# MS.net
KiCad netlist of a schematic drawn in Altium Designer
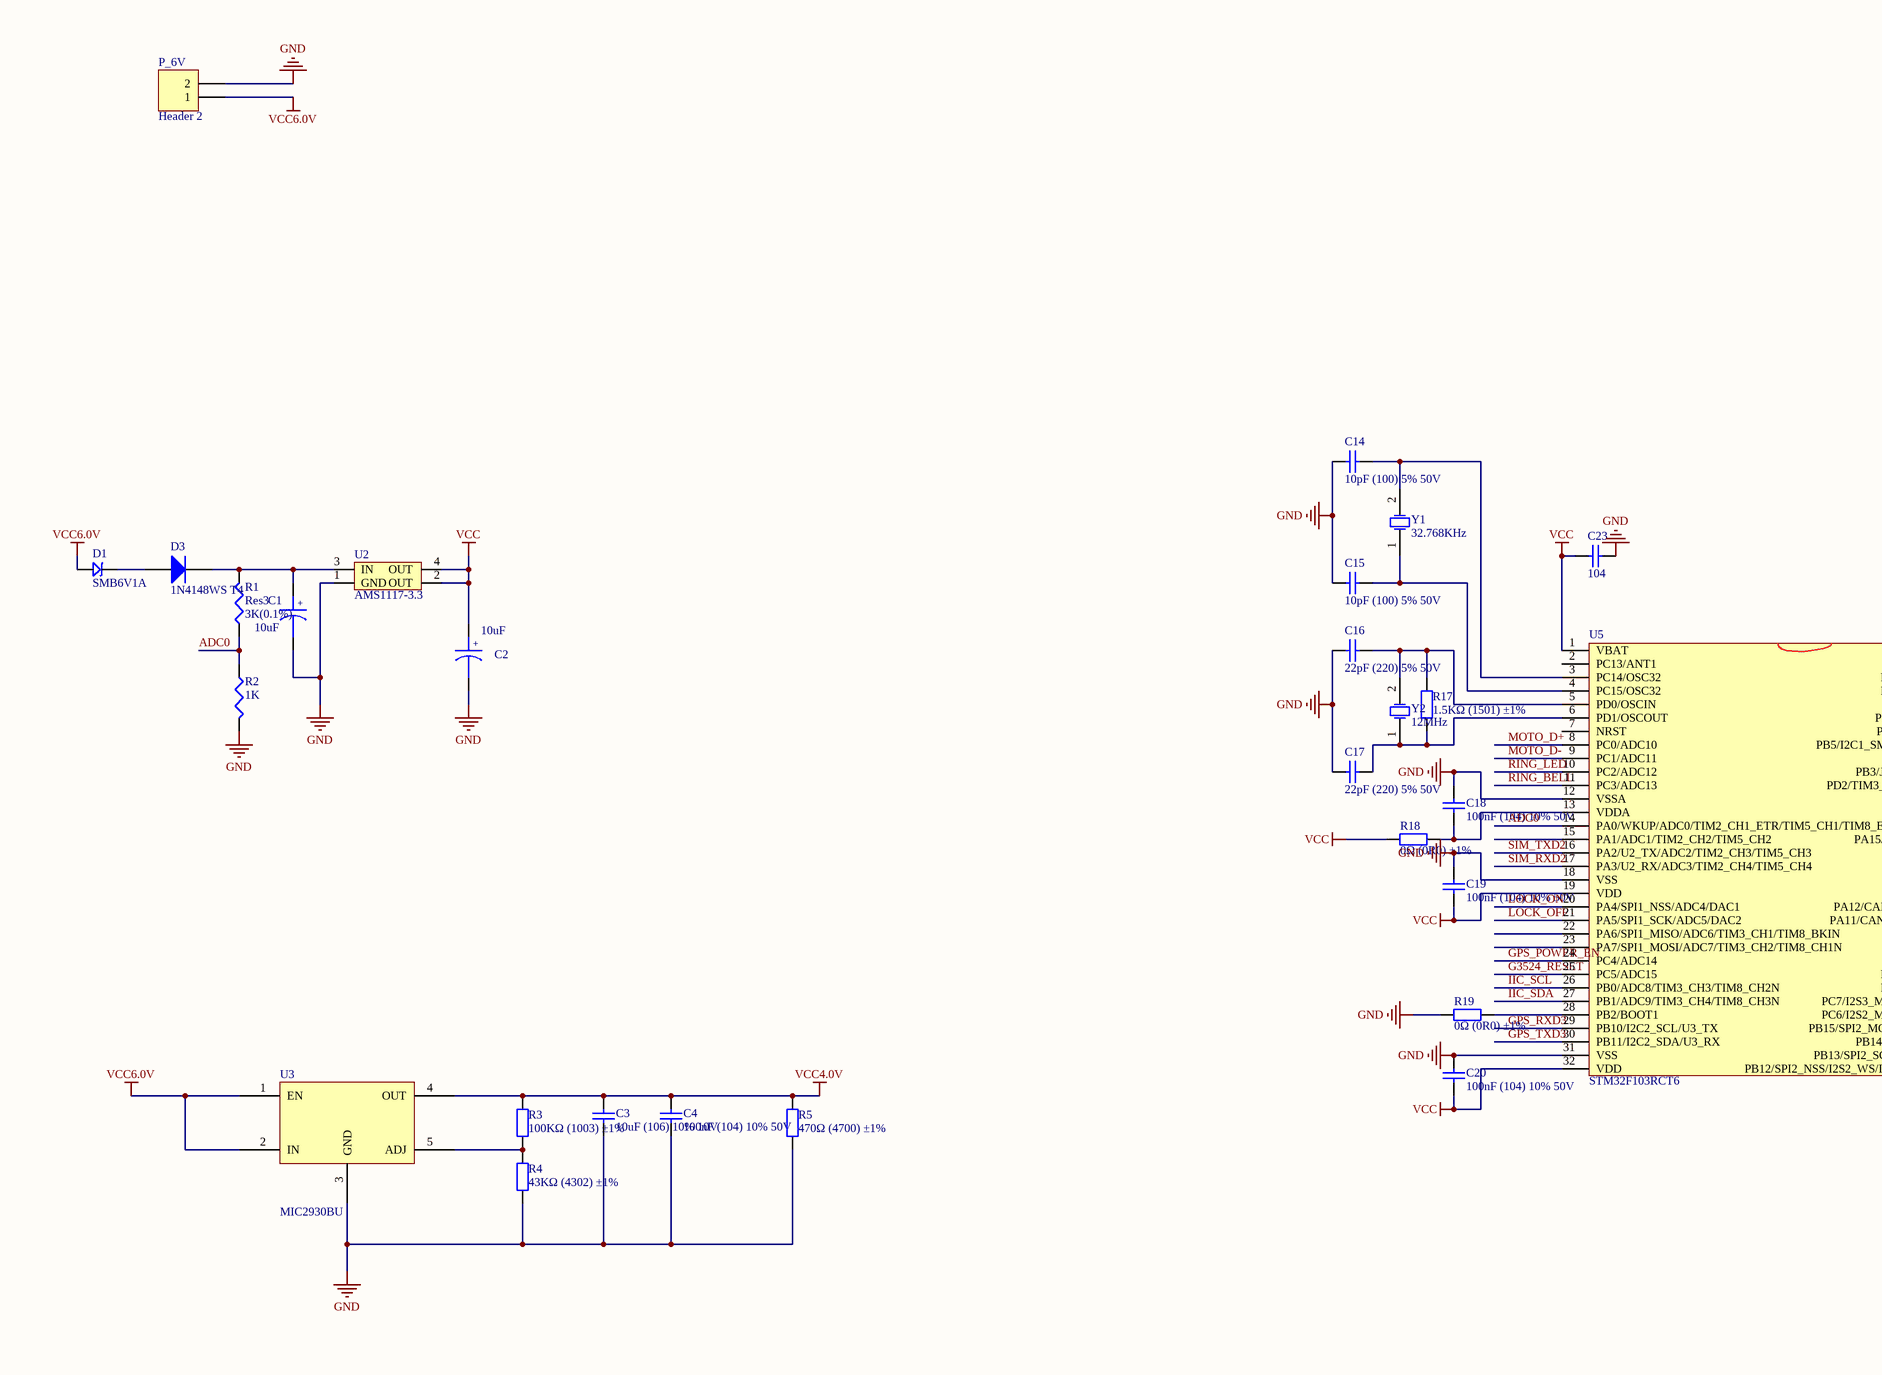
[diagram p0: MS.SchDoc, top left]
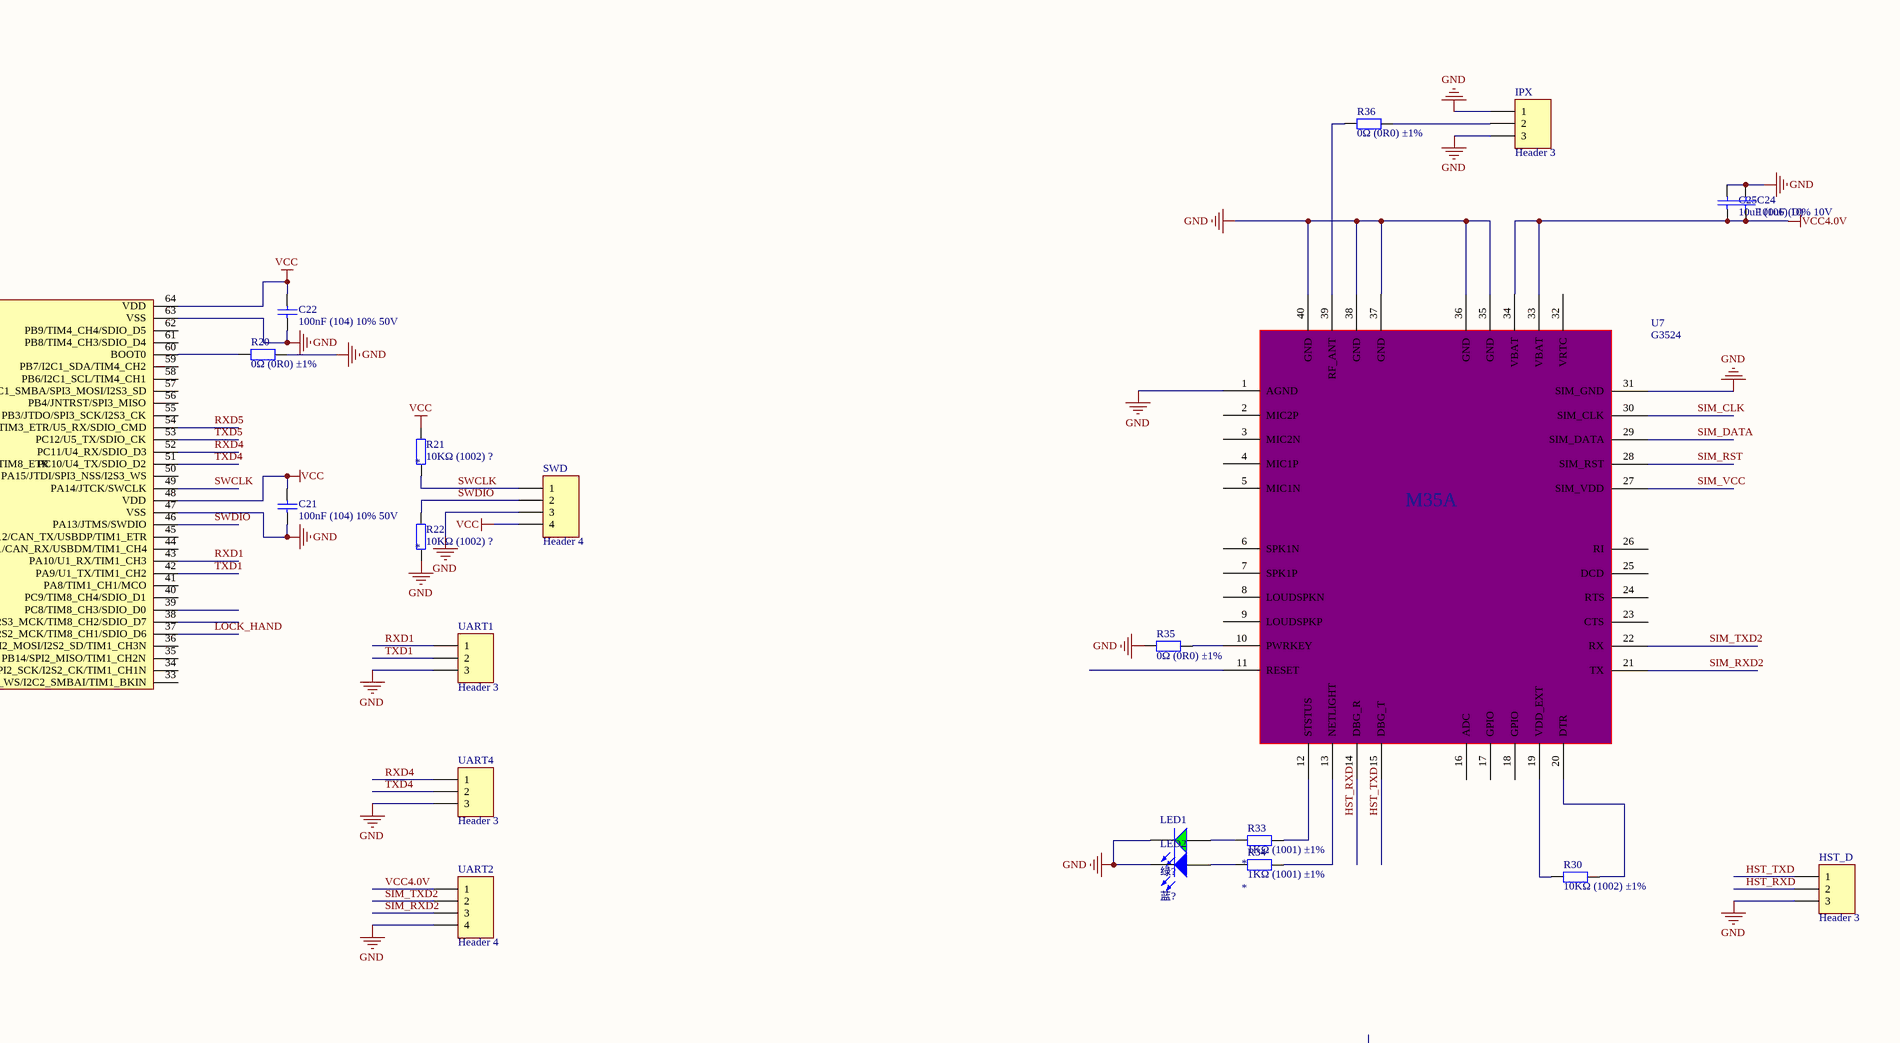
[diagram p1: MS.SchDoc, top right]
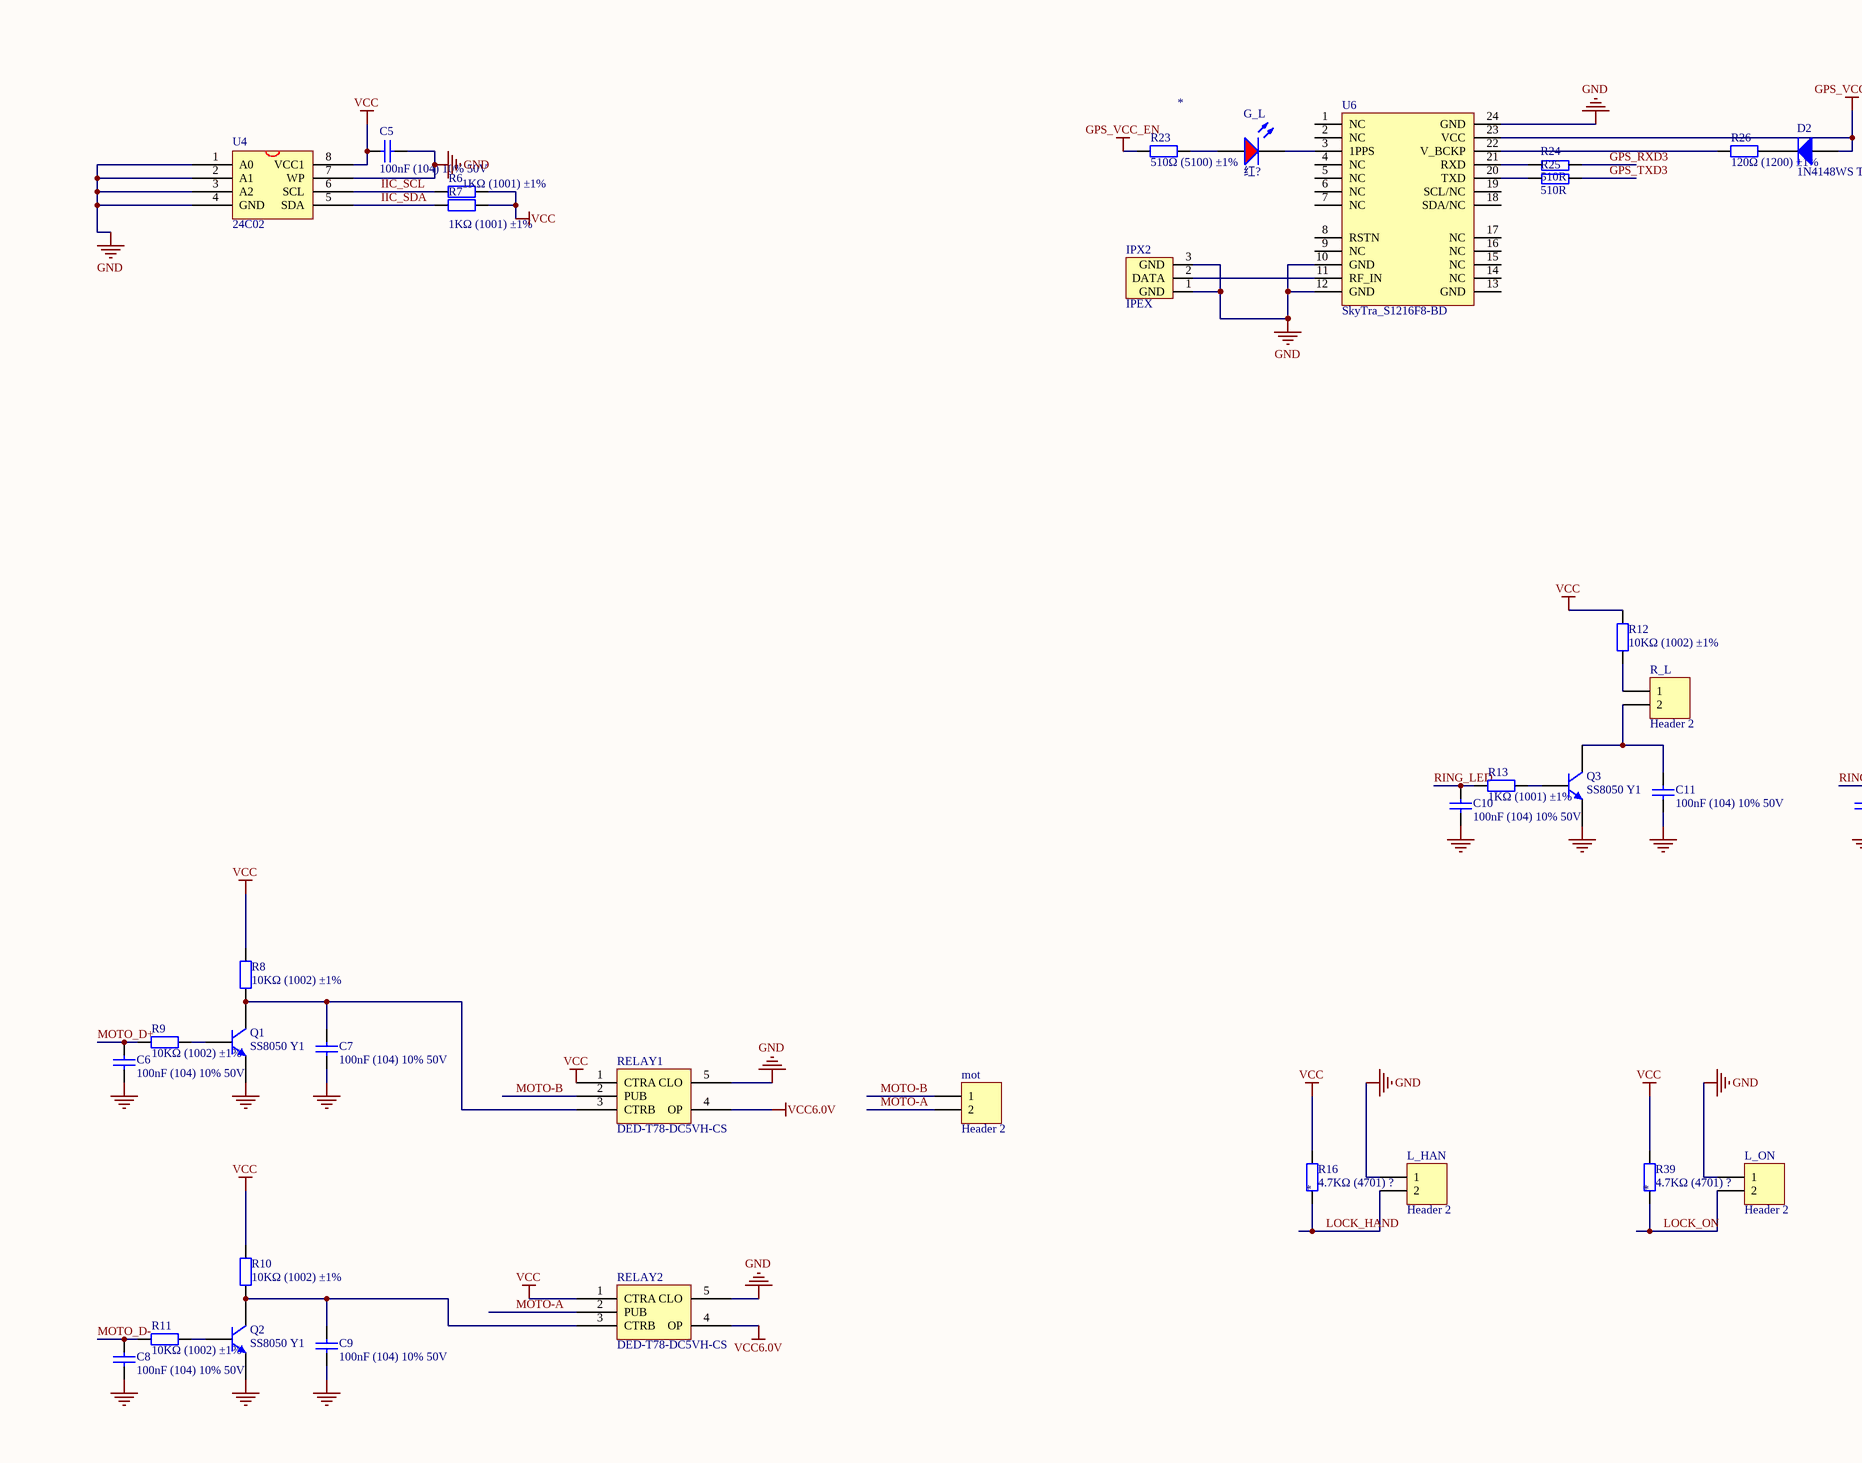
[diagram p2: MS.SchDoc, bottom left]
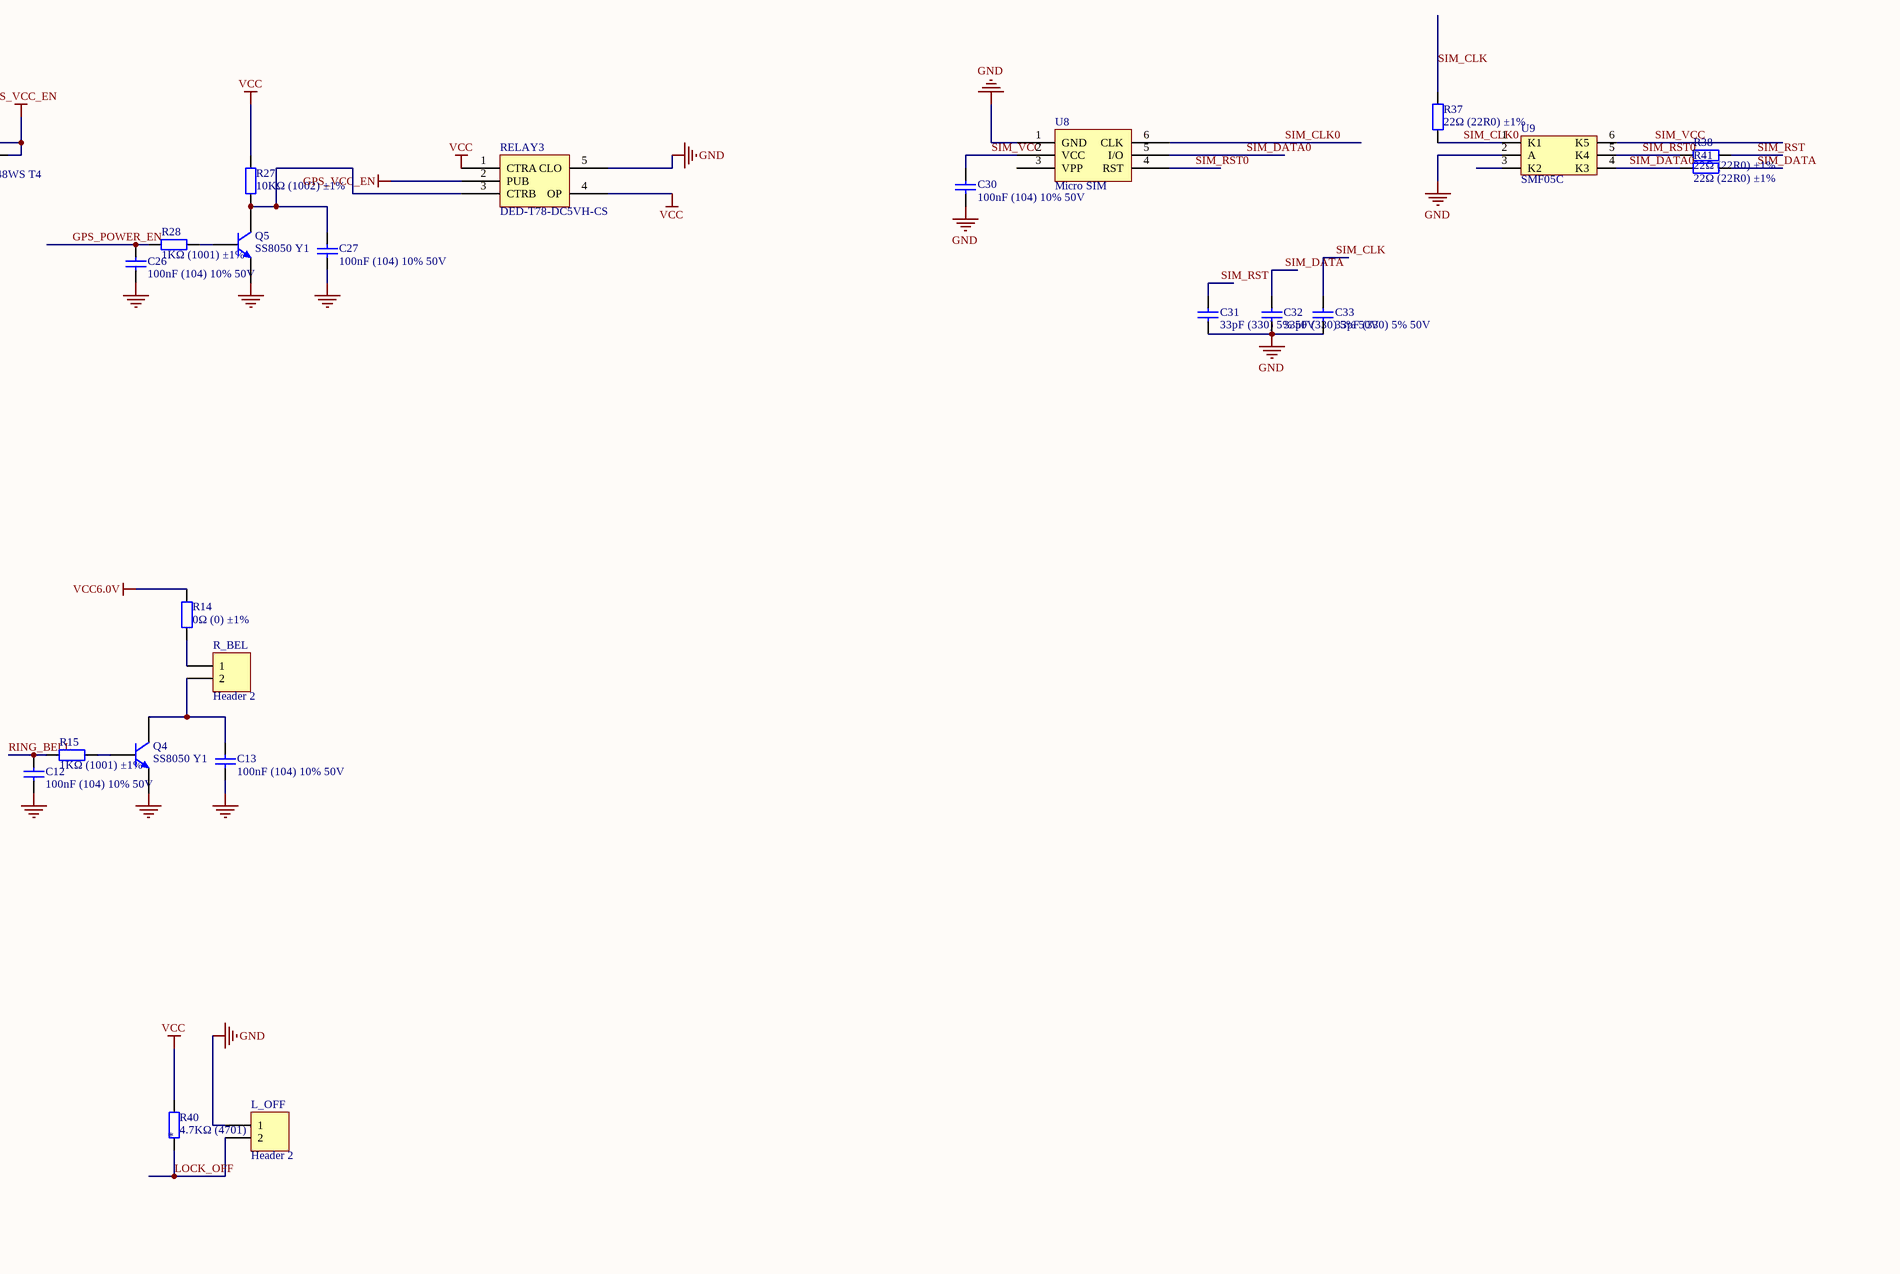
[diagram p3: MS.SchDoc, bottom right]

(export (version "E")
  (design (tool "Eeschema 10.0.6"))
  (components
    (comp (ref "C1")
      (value "10uF")
      (footprint "TANCAP")
      (description "Capacitor")
      (libsource (lib "*") (part "CAPACITOR POL"))
    )
    (comp (ref "C2")
      (value "10uF")
      (footprint "TANCAP")
      (description "Capacitor")
      (libsource (lib "*") (part "CAPACITOR POL"))
    )
    (comp (ref "C3")
      (value "10uF (106) 10% 10V")
      (footprint "0603_C")
      (description "贴片电容")
      (libsource (lib "Cap") (part "0603 10uF (106) 10% 10V"))
    )
    (comp (ref "C4")
      (value "100nF (104) 10% 50V")
      (footprint "0603_C")
      (description "贴片电容")
      (libsource (lib "Cap") (part "0603 100nF (104) 10% 50V"))
    )
    (comp (ref "C5")
      (value "100nF (104) 10% 50V")
      (footprint "0603_C")
      (description "贴片电容")
      (libsource (lib "Cap") (part "0603 100nF (104) 10% 50V"))
    )
    (comp (ref "C6")
      (value "100nF (104) 10% 50V")
      (footprint "0603_C")
      (description "贴片电容")
      (libsource (lib "Cap") (part "0603 100nF (104) 10% 50V"))
    )
    (comp (ref "C7")
      (value "100nF (104) 10% 50V")
      (footprint "0603_C")
      (description "贴片电容")
      (libsource (lib "Cap") (part "0603 100nF (104) 10% 50V"))
    )
    (comp (ref "C8")
      (value "100nF (104) 10% 50V")
      (footprint "0603_C")
      (description "贴片电容")
      (libsource (lib "Cap") (part "0603 100nF (104) 10% 50V"))
    )
    (comp (ref "C9")
      (value "100nF (104) 10% 50V")
      (footprint "0603_C")
      (description "贴片电容")
      (libsource (lib "Cap") (part "0603 100nF (104) 10% 50V"))
    )
    (comp (ref "C10")
      (value "100nF (104) 10% 50V")
      (footprint "0603_C")
      (description "贴片电容")
      (libsource (lib "Cap") (part "0603 100nF (104) 10% 50V"))
    )
    (comp (ref "C11")
      (value "100nF (104) 10% 50V")
      (footprint "0603_C")
      (description "贴片电容")
      (libsource (lib "Cap") (part "0603 100nF (104) 10% 50V"))
    )
    (comp (ref "C12")
      (value "100nF (104) 10% 50V")
      (footprint "0603_C")
      (description "贴片电容")
      (libsource (lib "Cap") (part "0603 100nF (104) 10% 50V"))
    )
    (comp (ref "C13")
      (value "100nF (104) 10% 50V")
      (footprint "0603_C")
      (description "贴片电容")
      (libsource (lib "Cap") (part "0603 100nF (104) 10% 50V"))
    )
    (comp (ref "C14")
      (value "10pF (100) 5% 50V")
      (footprint "0603_C")
      (description "贴片电容")
      (libsource (lib "Cap") (part "0603 10pF (100) 5% 50V"))
    )
    (comp (ref "C15")
      (value "10pF (100) 5% 50V")
      (footprint "0603_C")
      (description "贴片电容")
      (libsource (lib "Cap") (part "0603 10pF (100) 5% 50V"))
    )
    (comp (ref "C16")
      (value "22pF (220) 5% 50V")
      (footprint "0603_C")
      (description "贴片电容")
      (libsource (lib "Cap") (part "0603 22pF (220) 5% 50V"))
    )
    (comp (ref "C17")
      (value "22pF (220) 5% 50V")
      (footprint "0603_C")
      (description "贴片电容")
      (libsource (lib "Cap") (part "0603 22pF (220) 5% 50V"))
    )
    (comp (ref "C18")
      (value "100nF (104) 10% 50V")
      (footprint "0603_C")
      (description "贴片电容")
      (libsource (lib "Cap") (part "0603 100nF (104) 10% 50V"))
    )
    (comp (ref "C19")
      (value "100nF (104) 10% 50V")
      (footprint "0603_C")
      (description "贴片电容")
      (libsource (lib "Cap") (part "0603 100nF (104) 10% 50V"))
    )
    (comp (ref "C20")
      (value "100nF (104) 10% 50V")
      (footprint "0603_C")
      (description "贴片电容")
      (libsource (lib "Cap") (part "0603 100nF (104) 10% 50V"))
    )
    (comp (ref "C21")
      (value "100nF (104) 10% 50V")
      (footprint "0603_C")
      (description "贴片电容")
      (libsource (lib "Cap") (part "0603 100nF (104) 10% 50V"))
    )
    (comp (ref "C22")
      (value "100nF (104) 10% 50V")
      (footprint "0603_C")
      (description "贴片电容")
      (libsource (lib "Cap") (part "0603 100nF (104) 10% 50V"))
    )
    (comp (ref "C23")
      (value "104")
      (footprint "0603_C")
      (description "贴片电容")
      (libsource (lib "Cap") (part "0805 1uF (105) 10% 50V"))
    )
    (comp (ref "C24")
      (value "100uF (D)")
      (footprint "7343")
      (description "贴片电容")
      (libsource (lib "Cap") (part "0603 100nF (104) 10% 50V"))
    )
    (comp (ref "C25")
      (value "10uF (106) 10% 10V")
      (footprint "TanCap")
      (description "贴片电容")
      (libsource (lib "Cap") (part "0603 10uF (106) 10% 10V"))
    )
    (comp (ref "C26")
      (value "100nF (104) 10% 50V")
      (footprint "0603_C")
      (description "贴片电容")
      (libsource (lib "Cap") (part "0603 100nF (104) 10% 50V"))
    )
    (comp (ref "C27")
      (value "100nF (104) 10% 50V")
      (footprint "0603_C")
      (description "贴片电容")
      (libsource (lib "Cap") (part "0603 100nF (104) 10% 50V"))
    )
    (comp (ref "C30")
      (value "100nF (104) 10% 50V")
      (footprint "0603_C")
      (description "贴片电容")
      (libsource (lib "Cap") (part "0603 100nF (104) 10% 50V"))
    )
    (comp (ref "C31")
      (value "33pF (330) 5% 50V")
      (footprint "0603_C")
      (description "贴片电容")
      (libsource (lib "Cap") (part "0603 33pF (330) 5% 50V"))
    )
    (comp (ref "C32")
      (value "33pF (330) 5% 50V")
      (footprint "0603_C")
      (description "贴片电容")
      (libsource (lib "Cap") (part "0603 33pF (330) 5% 50V"))
    )
    (comp (ref "C33")
      (value "33pF (330) 5% 50V")
      (footprint "0603_C")
      (description "贴片电容")
      (libsource (lib "Cap") (part "0603 33pF (330) 5% 50V"))
    )
    (comp (ref "D1")
      (value "SMB6V1A")
      (footprint "1206")
      (description "TVS")
      (libsource (lib "WarShip V3 STM32103封装库") (part "SMBJ"))
    )
    (comp (ref "D2")
      (value "1N4148WS T4")
      (footprint "SOD-323")
      (description "二极管")
      (libsource (lib "Diode") (part "SOD-323 1N4148WS T4"))
    )
    (comp (ref "D3")
      (value "1N4148WS T4")
      (footprint "SOD-323")
      (description "二极管")
      (libsource (lib "Diode") (part "SOD-323 1N4148WS T4"))
    )
    (comp (ref "G_L")
      (value "*")
      (footprint "0603_LED_S1")
      (description "发光二极管")
      (fields (field (name "ALTIUM_UNNAMED_2") "红?"))
      (libsource (lib "LED") (part "0603 红灯"))
    )
    (comp (ref "HST_D")
      (value "Header 3")
      (footprint "HDR1X3")
      (description "Header, 3-Pin")
      (fields (field (name "PUBLISHER") "Altium Limited"))
      (libsource (lib "Miscellaneous Connectors") (part "Header 3"))
    )
    (comp (ref "IPX")
      (value "Header 3")
      (footprint "IPX")
      (description "Header, 3-Pin")
      (fields (field (name "PUBLISHER") "Altium Limited"))
      (libsource (lib "Miscellaneous Connectors") (part "Header 3"))
    )
    (comp (ref "IPX2")
      (value "IPEX")
      (footprint "IPEX")
      (description "IPEX座")
      (libsource (lib "S1216_1.1") (part "IPEX"))
    )
    (comp (ref "LED1")
      (value "*")
      (footprint "0603_LED_S1")
      (description "发光二极管")
      (fields (field (name "ALTIUM_UNNAMED_2") "绿?"))
      (libsource (lib "LED") (part "0603 绿灯"))
    )
    (comp (ref "LED2")
      (value "*")
      (footprint "0603_LED_S1")
      (description "发光二极管")
      (fields (field (name "ALTIUM_UNNAMED_2") "蓝?"))
      (libsource (lib "LED") (part "0603 蓝灯"))
    )
    (comp (ref "L_HAN")
      (value "Header 2")
      (footprint "COM2")
      (description "Header, 2-Pin")
      (fields (field (name "PUBLISHER") "Altium Limited"))
      (libsource (lib "Miscellaneous Connectors") (part "Header 2"))
    )
    (comp (ref "L_OFF")
      (value "Header 2")
      (footprint "COM2")
      (description "Header, 2-Pin")
      (fields (field (name "PUBLISHER") "Altium Limited"))
      (libsource (lib "Miscellaneous Connectors") (part "Header 2"))
    )
    (comp (ref "L_ON")
      (value "Header 2")
      (footprint "COM2")
      (description "Header, 2-Pin")
      (fields (field (name "PUBLISHER") "Altium Limited"))
      (libsource (lib "Miscellaneous Connectors") (part "Header 2"))
    )
    (comp (ref "mot")
      (value "Header 2")
      (footprint "COM2")
      (description "Header, 2-Pin")
      (fields (field (name "PUBLISHER") "Altium Limited"))
      (libsource (lib "Miscellaneous Connectors") (part "Header 2"))
    )
    (comp (ref "P_6V")
      (value "Header 2")
      (footprint "HEAD2L-0.8")
      (description "Header, 2-Pin")
      (fields (field (name "PUBLISHER") "Altium Limited"))
      (libsource (lib "") (part "Header 2_1"))
    )
    (comp (ref "Q1")
      (value "SS8050 Y1")
      (footprint "SOT-23(SOT-23-3)")
      (description "三极管")
      (libsource (lib "Transistor_NPN") (part "SOT-23 SS8050 Y1"))
    )
    (comp (ref "Q2")
      (value "SS8050 Y1")
      (footprint "SOT-23(SOT-23-3)")
      (description "三极管")
      (libsource (lib "Transistor_NPN") (part "SOT-23 SS8050 Y1"))
    )
    (comp (ref "Q3")
      (value "SS8050 Y1")
      (footprint "SOT-23(SOT-23-3)")
      (description "三极管")
      (libsource (lib "Transistor_NPN") (part "SOT-23 SS8050 Y1"))
    )
    (comp (ref "Q4")
      (value "SS8050 Y1")
      (footprint "SOT-23(SOT-23-3)")
      (description "三极管")
      (libsource (lib "Transistor_NPN") (part "SOT-23 SS8050 Y1"))
    )
    (comp (ref "Q5")
      (value "SS8050 Y1")
      (footprint "SOT-23(SOT-23-3)")
      (description "三极管")
      (libsource (lib "Transistor_NPN") (part "SOT-23 SS8050 Y1"))
    )
    (comp (ref "R1")
      (value "Res3")
      (footprint "AXIAL-0.3")
      (description "Resistor")
      (fields (field (name "ALTIUM_VALUE") "3K(0.1%)") (field (name "PUBLISHER") "Altium Limited"))
      (libsource (lib "Miscellaneous Devices") (part "Res3"))
    )
    (comp (ref "R2")
      (value "1K")
      (footprint "AXIAL-0.3")
      (description "Resistor")
      (fields (field (name "PUBLISHER") "Altium Limited"))
      (libsource (lib "Miscellaneous Devices") (part "Res3"))
    )
    (comp (ref "R3")
      (value "100KΩ (1003) ±1%")
      (footprint "0603_R")
      (description "贴片电阻")
      (libsource (lib "RES") (part "0603 100KΩ (1003) 1%"))
    )
    (comp (ref "R4")
      (value "43KΩ (4302) ±1%")
      (footprint "0603_R")
      (description "贴片电阻")
      (libsource (lib "RES") (part "0603 43KΩ (4302) 1%"))
    )
    (comp (ref "R5")
      (value "470Ω (4700) ±1%")
      (footprint "0603_R")
      (description "贴片电阻")
      (libsource (lib "RES") (part "0603 470Ω (4700) 1%"))
    )
    (comp (ref "R6")
      (value "1KΩ (1001) ±1%")
      (footprint "0603_R")
      (description "贴片电阻")
      (libsource (lib "RES") (part "0603 1KΩ (1001) 1%"))
    )
    (comp (ref "R7")
      (value "1KΩ (1001) ±1%")
      (footprint "0603_R")
      (description "贴片电阻")
      (libsource (lib "RES") (part "0603 1KΩ (1001) 1%"))
    )
    (comp (ref "R8")
      (value "10KΩ (1002) ±1%")
      (footprint "0603_R")
      (description "贴片电阻")
      (libsource (lib "RES") (part "0603 10KΩ (1002) 1%"))
    )
    (comp (ref "R9")
      (value "10KΩ (1002) ±1%")
      (footprint "0603_R")
      (description "贴片电阻")
      (libsource (lib "") (part "0603 10KΩ (1002) 1%_1"))
    )
    (comp (ref "R10")
      (value "10KΩ (1002) ±1%")
      (footprint "0603_R")
      (description "贴片电阻")
      (libsource (lib "RES") (part "0603 10KΩ (1002) 1%"))
    )
    (comp (ref "R11")
      (value "10KΩ (1002) ±1%")
      (footprint "0603_R")
      (description "贴片电阻")
      (libsource (lib "") (part "0603 10KΩ (1002) 1%_1"))
    )
    (comp (ref "R12")
      (value "10KΩ (1002) ±1%")
      (footprint "0603_R")
      (description "贴片电阻")
      (libsource (lib "RES") (part "0603 10KΩ (1002) 1%"))
    )
    (comp (ref "R13")
      (value "1KΩ (1001) ±1%")
      (footprint "0603_R")
      (description "贴片电阻")
      (libsource (lib "RES") (part "0603 1KΩ (1001) 1%"))
    )
    (comp (ref "R14")
      (value "0Ω (0) ±1%")
      (footprint "0603_R")
      (description "贴片电阻")
      (libsource (lib "RES") (part "0603 10KΩ (1002) 1%"))
    )
    (comp (ref "R15")
      (value "1KΩ (1001) ±1%")
      (footprint "0603_R")
      (description "贴片电阻")
      (libsource (lib "RES") (part "0603 1KΩ (1001) 1%"))
    )
    (comp (ref "R16")
      (value "*")
      (footprint "0603_R")
      (description "贴片电阻")
      (fields (field (name "ALTIUM_UNNAMED_2") "4.7KΩ (4701) ?"))
      (libsource (lib "RES") (part "0603 4.7KΩ (4701) 1%"))
    )
    (comp (ref "R17")
      (value "1.5KΩ (1501) ±1%")
      (footprint "0603_R")
      (description "贴片电阻")
      (libsource (lib "RES") (part "0603 1.5KΩ (1501) 1%"))
    )
    (comp (ref "R18")
      (value "0Ω (0R0) ±1%")
      (footprint "0603_R")
      (description "贴片电阻")
      (libsource (lib "RES") (part "0603 0Ω (0R0) 1%"))
    )
    (comp (ref "R19")
      (value "0Ω (0R0) ±1%")
      (footprint "0603_R")
      (description "贴片电阻")
      (libsource (lib "RES") (part "0603 0Ω (0R0) 1%"))
    )
    (comp (ref "R20")
      (value "0Ω (0R0) ±1%")
      (footprint "0603_R")
      (description "贴片电阻")
      (libsource (lib "RES") (part "0603 0Ω (0R0) 1%"))
    )
    (comp (ref "R21")
      (value "*")
      (footprint "0603_R")
      (description "贴片电阻")
      (fields (field (name "ALTIUM_UNNAMED_2") "10KΩ (1002) ?"))
      (libsource (lib "RES") (part "0603 10KΩ (1002) 1%"))
    )
    (comp (ref "R22")
      (value "*")
      (footprint "0603_R")
      (description "贴片电阻")
      (fields (field (name "ALTIUM_UNNAMED_2") "10KΩ (1002) ?"))
      (libsource (lib "RES") (part "0603 10KΩ (1002) 1%"))
    )
    (comp (ref "R23")
      (value "510Ω (5100) ±1%")
      (footprint "0603_R")
      (description "贴片电阻")
      (libsource (lib "RES") (part "0603 510Ω (5100) 1%"))
    )
    (comp (ref "R24") (value "510R") (footprint "0603_R") (libsource (lib "S1216_1.1") (part "R")))
    (comp (ref "R25") (value "510R") (footprint "0603_R") (libsource (lib "S1216_1.1") (part "R")))
    (comp (ref "R26")
      (value "120Ω (1200) ±1%")
      (footprint "0603_R")
      (description "贴片电阻")
      (libsource (lib "RES") (part "0603 120Ω (1200) 1%"))
    )
    (comp (ref "R27")
      (value "10KΩ (1002) ±1%")
      (footprint "0603_R")
      (description "贴片电阻")
      (libsource (lib "RES") (part "0603 10KΩ (1002) 1%"))
    )
    (comp (ref "R28")
      (value "1KΩ (1001) ±1%")
      (footprint "0603_R")
      (description "贴片电阻")
      (libsource (lib "RES") (part "0603 1KΩ (1001) 1%"))
    )
    (comp (ref "R30")
      (value "10KΩ (1002) ±1%")
      (footprint "0603_R")
      (description "贴片电阻")
      (libsource (lib "") (part "0603 10KΩ (1002) 1%_1"))
    )
    (comp (ref "R33")
      (value "1KΩ (1001) ±1%")
      (footprint "0603_R")
      (description "贴片电阻")
      (libsource (lib "RES") (part "0603 1KΩ (1001) 1%"))
    )
    (comp (ref "R34")
      (value "1KΩ (1001) ±1%")
      (footprint "0603_R")
      (description "贴片电阻")
      (libsource (lib "RES") (part "0603 1KΩ (1001) 1%"))
    )
    (comp (ref "R35")
      (value "0Ω (0R0) ±1%")
      (footprint "0603_R")
      (description "贴片电阻")
      (libsource (lib "") (part "0603 0Ω (0R0) 1%_1"))
    )
    (comp (ref "R36")
      (value "0Ω (0R0) ±1%")
      (footprint "0603_R")
      (description "贴片电阻")
      (libsource (lib "RES") (part "0603 0Ω (0R0) 1%"))
    )
    (comp (ref "R37")
      (value "22Ω (22R0) ±1%")
      (footprint "0603_R")
      (description "贴片电阻")
      (libsource (lib "RES") (part "0603 22Ω (22R0) 1%"))
    )
    (comp (ref "R38")
      (value "22Ω (22R0) ±1%")
      (footprint "0603_R")
      (description "贴片电阻")
      (libsource (lib "") (part "0603 22Ω (22R0) 1%_1"))
    )
    (comp (ref "R39")
      (value "*")
      (footprint "0603_R")
      (description "贴片电阻")
      (fields (field (name "ALTIUM_UNNAMED_2") "4.7KΩ (4701) ?"))
      (libsource (lib "RES") (part "0603 4.7KΩ (4701) 1%"))
    )
    (comp (ref "R40")
      (value "*")
      (footprint "0603_R")
      (description "贴片电阻")
      (fields (field (name "ALTIUM_UNNAMED_2") "4.7KΩ (4701) ?"))
      (libsource (lib "RES") (part "0603 4.7KΩ (4701) 1%"))
    )
    (comp (ref "R41")
      (value "22Ω (22R0) ±1%")
      (footprint "0603_R")
      (description "贴片电阻")
      (libsource (lib "") (part "0603 22Ω (22R0) 1%_1"))
    )
    (comp (ref "RELAY1")
      (value "DED-T78-DC5VH-CS")
      (footprint "SRA-05VDC-CL")
      (libsource (lib "Ms_schlib") (part "DED-T78-DC5VH-CS"))
    )
    (comp (ref "RELAY2")
      (value "DED-T78-DC5VH-CS")
      (footprint "SRA-05VDC-CL")
      (libsource (lib "Ms_schlib") (part "DED-T78-DC5VH-CS"))
    )
    (comp (ref "RELAY3")
      (value "DED-T78-DC5VH-CS")
      (footprint "SRA-05VDC-CL")
      (libsource (lib "Ms_schlib") (part "DED-T78-DC5VH-CS"))
    )
    (comp (ref "R_BEL")
      (value "Header 2")
      (footprint "COM2")
      (description "Header, 2-Pin")
      (fields (field (name "PUBLISHER") "Altium Limited"))
      (libsource (lib "Miscellaneous Connectors") (part "Header 2"))
    )
    (comp (ref "R_L")
      (value "Header 2")
      (footprint "COM2")
      (description "Header, 2-Pin")
      (fields (field (name "PUBLISHER") "Altium Limited"))
      (libsource (lib "Miscellaneous Connectors") (part "Header 2"))
    )
    (comp (ref "SWD")
      (value "Header 4")
      (footprint "HDR1X4")
      (description "Header, 4-Pin")
      (fields (field (name "PUBLISHER") "Altium Limited"))
      (libsource (lib "Miscellaneous Connectors") (part "Header 4"))
    )
    (comp (ref "U2")
      (value "AMS1117-3.3")
      (footprint "AMS1117")
      (libsource (lib "EXPLORER") (part "AMS1117"))
    )
    (comp (ref "U3") (value "MIC2930BU") (libsource (lib "Ms_schlib") (part "MIC2930BU")))
    (comp (ref "U4") (value "24C02") (footprint "SOP-8") (libsource (lib "EXPLORER") (part "24C256")))
    (comp (ref "U5")
      (value "STM32F103RCT6")
      (footprint "LC-LQFP-64_10x10x05P")
      (libsource (lib "MiniSTM32 V3.0封装库") (part "STM32F103RDT6"))
    )
    (comp (ref "U6")
      (value "SkyTra_S1216F8-BD")
      (footprint "S1216_V1.1:GPS_NEO-6")
      (libsource (lib "S1216_1.1") (part "SkyTra_GPS"))
    )
    (comp (ref "U7")
      (value "G3524")
      (footprint "PCBComponent_1")
      (libsource (lib "G3524_SCH") (part "Component_1"))
    )
    (comp (ref "U8") (value "Micro SIM") (libsource (lib "ATK-SIM800C") (part "Micro SIM")))
    (comp (ref "U9")
      (value "SMF05C")
      (footprint "SMF05C")
      (description "TVS")
      (libsource (lib "ATK-SIM800C") (part "SMF05C"))
    )
    (comp (ref "UART1")
      (value "Header 3")
      (footprint "HDR1X3")
      (description "Header, 3-Pin")
      (fields (field (name "PUBLISHER") "Altium Limited"))
      (libsource (lib "Miscellaneous Connectors") (part "Header 3"))
    )
    (comp (ref "UART2")
      (value "Header 4")
      (footprint "HDR1X4")
      (description "Header, 4-Pin")
      (fields (field (name "PUBLISHER") "Altium Limited"))
      (libsource (lib "Miscellaneous Connectors") (part "Header 4"))
    )
    (comp (ref "UART4")
      (value "Header 3")
      (footprint "HDR1X3")
      (description "Header, 3-Pin")
      (fields (field (name "PUBLISHER") "Altium Limited"))
      (libsource (lib "Miscellaneous Connectors") (part "Header 3"))
    )
    (comp (ref "Y1")
      (value "32.768KHz")
      (footprint "XTAL32")
      (description "Crystal Oscillator")
      (fields (field (name "PUBLISHER") "Altium Limited"))
      (libsource (lib "MiniSTM32 V3.0封装库") (part "XTAL"))
    )
    (comp (ref "Y2")
      (value "12MHz")
      (footprint "XTAL_US")
      (description "Crystal Oscillator")
      (fields (field (name "PUBLISHER") "Altium Limited"))
      (libsource (lib "MiniSTM32 V3.0封装库") (part "XTAL"))
    )
  )
  (nets
    (net (code "1") (name "/ADC0") (class "Default")
      (node (ref "R1") (pin "1") (pinfunction "1_1") (pintype "passive"))
      (node (ref "R2") (pin "1") (pinfunction "1_1") (pintype "passive"))
      (node (ref "U5") (pin "14") (pinfunction "PA0/WKUP/ADC0/TIM2_CH1_ETR/TIM5_CH1/TIM8_ETR_14") (pintype "passive"))
    )
    (net (code "2") (name "/G3524_RESET") (class "Default")
      (node (ref "U5") (pin "25") (pinfunction "PC5/ADC15_25") (pintype "passive"))
    )
    (net (code "3") (name "/GPS_POWER_EN") (class "Default")
      (node (ref "C26") (pin "2") (pinfunction "2_2") (pintype "passive"))
      (node (ref "R28") (pin "1") (pinfunction "1_1") (pintype "passive"))
      (node (ref "U5") (pin "24") (pinfunction "PC4/ADC14_24") (pintype "passive"))
    )
    (net (code "4") (name "/GPS_RXD3") (class "Default")
      (node (ref "R24") (pin "2") (pintype "passive"))
      (node (ref "U5") (pin "29") (pinfunction "PB10/I2C2_SCL/U3_TX_29") (pintype "passive"))
    )
    (net (code "5") (name "/GPS_TXD3") (class "Default")
      (node (ref "R25") (pin "2") (pintype "passive"))
      (node (ref "U5") (pin "30") (pinfunction "PB11/I2C2_SDA/U3_RX_30") (pintype "passive"))
    )
    (net (code "6") (name "/HST_RXD") (class "Default")
      (node (ref "HST_D") (pin "2") (pinfunction "2_2") (pintype "passive"))
      (node (ref "U7") (pin "14") (pinfunction "DBG_R_14") (pintype "passive"))
    )
    (net (code "7") (name "/HST_TXD") (class "Default")
      (node (ref "HST_D") (pin "1") (pinfunction "1_1") (pintype "passive"))
      (node (ref "U7") (pin "15") (pinfunction "DBG_T_15") (pintype "passive"))
    )
    (net (code "8") (name "/IIC_SCL") (class "Default")
      (node (ref "R6") (pin "1") (pinfunction "1_1") (pintype "passive"))
      (node (ref "U4") (pin "6") (pinfunction "SCL_6") (pintype "passive"))
      (node (ref "U5") (pin "26") (pinfunction "PB0/ADC8/TIM3_CH3/TIM8_CH2N_26") (pintype "passive"))
    )
    (net (code "9") (name "/IIC_SDA") (class "Default")
      (node (ref "R7") (pin "1") (pinfunction "1_1") (pintype "passive"))
      (node (ref "U4") (pin "5") (pinfunction "SDA_5") (pintype "passive"))
      (node (ref "U5") (pin "27") (pinfunction "PB1/ADC9/TIM3_CH4/TIM8_CH3N_27") (pintype "passive"))
    )
    (net (code "10") (name "/LOCK_HAND") (class "Default")
      (node (ref "L_HAN") (pin "2") (pinfunction "2_2") (pintype "passive"))
      (node (ref "R16") (pin "1") (pinfunction "1_1") (pintype "passive"))
      (node (ref "U5") (pin "37") (pinfunction "PC6/I2S2_MCK/TIM8_CH1/SDIO_D6_37") (pintype "passive"))
    )
    (net (code "11") (name "/LOCK_OFF") (class "Default")
      (node (ref "L_OFF") (pin "2") (pinfunction "2_2") (pintype "passive"))
      (node (ref "R40") (pin "1") (pinfunction "1_1") (pintype "passive"))
      (node (ref "U5") (pin "21") (pinfunction "PA5/SPI1_SCK/ADC5/DAC2_21") (pintype "passive"))
    )
    (net (code "12") (name "/LOCK_ON") (class "Default")
      (node (ref "L_ON") (pin "2") (pinfunction "2_2") (pintype "passive"))
      (node (ref "R39") (pin "1") (pinfunction "1_1") (pintype "passive"))
      (node (ref "U5") (pin "20") (pinfunction "PA4/SPI1_NSS/ADC4/DAC1_20") (pintype "passive"))
    )
    (net (code "13") (name "/MOTO-A") (class "Default")
      (node (ref "RELAY2") (pin "2") (pinfunction "PUB_2") (pintype "passive"))
      (node (ref "mot") (pin "2") (pinfunction "2_2") (pintype "passive"))
    )
    (net (code "14") (name "/MOTO-B") (class "Default")
      (node (ref "RELAY1") (pin "2") (pinfunction "PUB_2") (pintype "passive"))
      (node (ref "mot") (pin "1") (pinfunction "1_1") (pintype "passive"))
    )
    (net (code "15") (name "/MOTO_D+") (class "Default")
      (node (ref "C6") (pin "2") (pinfunction "2_2") (pintype "passive"))
      (node (ref "R9") (pin "1") (pinfunction "1_1") (pintype "passive"))
      (node (ref "U5") (pin "8") (pinfunction "PC0/ADC10_8") (pintype "passive"))
    )
    (net (code "16") (name "/MOTO_D-") (class "Default")
      (node (ref "C8") (pin "2") (pinfunction "2_2") (pintype "passive"))
      (node (ref "R11") (pin "1") (pinfunction "1_1") (pintype "passive"))
      (node (ref "U5") (pin "9") (pinfunction "PC1/ADC11_9") (pintype "passive"))
    )
    (net (code "17") (name "/RING_BELL") (class "Default")
      (node (ref "C12") (pin "2") (pinfunction "2_2") (pintype "passive"))
      (node (ref "R15") (pin "1") (pinfunction "1_1") (pintype "passive"))
      (node (ref "U5") (pin "11") (pinfunction "PC3/ADC13_11") (pintype "passive"))
    )
    (net (code "18") (name "/RING_LED") (class "Default")
      (node (ref "C10") (pin "2") (pinfunction "2_2") (pintype "passive"))
      (node (ref "R13") (pin "1") (pinfunction "1_1") (pintype "passive"))
      (node (ref "U5") (pin "10") (pinfunction "PC2/ADC12_10") (pintype "passive"))
    )
    (net (code "19") (name "/RXD1") (class "Default")
      (node (ref "U5") (pin "43") (pinfunction "PA10/U1_RX/TIM1_CH3_43") (pintype "passive"))
      (node (ref "UART1") (pin "1") (pinfunction "1_1") (pintype "passive"))
    )
    (net (code "20") (name "/RXD4") (class "Default")
      (node (ref "U5") (pin "52") (pinfunction "PC11/U4_RX/SDIO_D3_52") (pintype "passive"))
      (node (ref "UART4") (pin "1") (pinfunction "1_1") (pintype "passive"))
    )
    (net (code "21") (name "/RXD5") (class "Default")
      (node (ref "U5") (pin "54") (pinfunction "PD2/TIM3_ETR/U5_RX/SDIO_CMD_54") (pintype "passive"))
    )
    (net (code "22") (name "/SIM_CLK") (class "Default")
      (node (ref "C33") (pin "2") (pinfunction "2_2") (pintype "passive"))
      (node (ref "R37") (pin "2") (pinfunction "2_2") (pintype "passive"))
      (node (ref "U7") (pin "30") (pinfunction "SIM_CLK_30") (pintype "passive"))
    )
    (net (code "23") (name "/SIM_CLK0") (class "Default")
      (node (ref "R37") (pin "1") (pinfunction "1_1") (pintype "passive"))
      (node (ref "U8") (pin "6") (pinfunction "CLK_6") (pintype "passive"))
      (node (ref "U9") (pin "1") (pinfunction "K1_1") (pintype "passive"))
    )
    (net (code "24") (name "/SIM_DATA") (class "Default")
      (node (ref "C32") (pin "2") (pinfunction "2_2") (pintype "passive"))
      (node (ref "R41") (pin "2") (pinfunction "2_2") (pintype "passive"))
      (node (ref "U7") (pin "29") (pinfunction "SIM_DATA_29") (pintype "passive"))
    )
    (net (code "25") (name "/SIM_DATA0") (class "Default")
      (node (ref "R41") (pin "1") (pinfunction "1_1") (pintype "passive"))
      (node (ref "U8") (pin "5") (pinfunction "I/O_5") (pintype "passive"))
      (node (ref "U9") (pin "4") (pinfunction "K3_4") (pintype "passive"))
    )
    (net (code "26") (name "/SIM_RST") (class "Default")
      (node (ref "C31") (pin "2") (pinfunction "2_2") (pintype "passive"))
      (node (ref "R38") (pin "2") (pinfunction "2_2") (pintype "passive"))
      (node (ref "U7") (pin "28") (pinfunction "SIM_RST_28") (pintype "passive"))
    )
    (net (code "27") (name "/SIM_RST0") (class "Default")
      (node (ref "R38") (pin "1") (pinfunction "1_1") (pintype "passive"))
      (node (ref "U8") (pin "4") (pinfunction "RST_4") (pintype "passive"))
      (node (ref "U9") (pin "5") (pinfunction "K4_5") (pintype "passive"))
    )
    (net (code "28") (name "/SIM_RXD2") (class "Default")
      (node (ref "U5") (pin "17") (pinfunction "PA3/U2_RX/ADC3/TIM2_CH4/TIM5_CH4_17") (pintype "passive"))
      (node (ref "U7") (pin "21") (pinfunction "TX_21") (pintype "passive"))
      (node (ref "UART2") (pin "3") (pinfunction "3_3") (pintype "passive"))
    )
    (net (code "29") (name "/SIM_TXD2") (class "Default")
      (node (ref "U5") (pin "16") (pinfunction "PA2/U2_TX/ADC2/TIM2_CH3/TIM5_CH3_16") (pintype "passive"))
      (node (ref "U7") (pin "22") (pinfunction "RX_22") (pintype "passive"))
      (node (ref "UART2") (pin "2") (pinfunction "2_2") (pintype "passive"))
    )
    (net (code "30") (name "/SIM_VCC") (class "Default")
      (node (ref "C30") (pin "2") (pinfunction "2_2") (pintype "passive"))
      (node (ref "U7") (pin "27") (pinfunction "SIM_VDD_27") (pintype "passive"))
      (node (ref "U8") (pin "2") (pinfunction "VCC_2") (pintype "passive"))
      (node (ref "U9") (pin "6") (pinfunction "K5_6") (pintype "passive"))
    )
    (net (code "31") (name "/SWCLK") (class "Default")
      (node (ref "R21") (pin "1") (pinfunction "1_1") (pintype "passive"))
      (node (ref "SWD") (pin "1") (pinfunction "1_1") (pintype "passive"))
      (node (ref "U5") (pin "49") (pinfunction "PA14/JTCK/SWCLK_49") (pintype "passive"))
    )
    (net (code "32") (name "/SWDIO") (class "Default")
      (node (ref "R22") (pin "2") (pinfunction "2_2") (pintype "passive"))
      (node (ref "SWD") (pin "2") (pinfunction "2_2") (pintype "passive"))
      (node (ref "U5") (pin "46") (pinfunction "PA13/JTMS/SWDIO_46") (pintype "passive"))
    )
    (net (code "33") (name "/TXD1") (class "Default")
      (node (ref "U5") (pin "42") (pinfunction "PA9/U1_TX/TIM1_CH2_42") (pintype "passive"))
      (node (ref "UART1") (pin "2") (pinfunction "2_2") (pintype "passive"))
    )
    (net (code "34") (name "/TXD4") (class "Default")
      (node (ref "U5") (pin "51") (pinfunction "PC10/U4_TX/SDIO_D2_51") (pintype "passive"))
      (node (ref "UART4") (pin "2") (pinfunction "2_2") (pintype "passive"))
    )
    (net (code "35") (name "/TXD5") (class "Default")
      (node (ref "U5") (pin "53") (pinfunction "PC12/U5_TX/SDIO_CK_53") (pintype "passive"))
    )
    (net (code "36") (name "GND") (class "Default")
      (node (ref "C1") (pin "2") (pinfunction "2_2") (pintype "passive"))
      (node (ref "C10") (pin "1") (pinfunction "1_1") (pintype "passive"))
      (node (ref "C11") (pin "1") (pinfunction "1_1") (pintype "passive"))
      (node (ref "C12") (pin "1") (pinfunction "1_1") (pintype "passive"))
      (node (ref "C13") (pin "1") (pinfunction "1_1") (pintype "passive"))
      (node (ref "C14") (pin "1") (pinfunction "1_1") (pintype "passive"))
      (node (ref "C15") (pin "1") (pinfunction "1_1") (pintype "passive"))
      (node (ref "C16") (pin "1") (pinfunction "1_1") (pintype "passive"))
      (node (ref "C17") (pin "1") (pinfunction "1_1") (pintype "passive"))
      (node (ref "C18") (pin "1") (pinfunction "1_1") (pintype "passive"))
      (node (ref "C19") (pin "1") (pinfunction "1_1") (pintype "passive"))
      (node (ref "C2") (pin "2") (pinfunction "2_2") (pintype "passive"))
      (node (ref "C20") (pin "1") (pinfunction "1_1") (pintype "passive"))
      (node (ref "C21") (pin "2") (pinfunction "2_2") (pintype "passive"))
      (node (ref "C22") (pin "1") (pinfunction "1_1") (pintype "passive"))
      (node (ref "C23") (pin "1") (pinfunction "1_1") (pintype "passive"))
      (node (ref "C24") (pin "2") (pinfunction "2_2") (pintype "passive"))
      (node (ref "C25") (pin "2") (pinfunction "2_2") (pintype "passive"))
      (node (ref "C26") (pin "1") (pinfunction "1_1") (pintype "passive"))
      (node (ref "C27") (pin "1") (pinfunction "1_1") (pintype "passive"))
      (node (ref "C3") (pin "1") (pinfunction "1_1") (pintype "passive"))
      (node (ref "C30") (pin "1") (pinfunction "1_1") (pintype "passive"))
      (node (ref "C31") (pin "1") (pinfunction "1_1") (pintype "passive"))
      (node (ref "C32") (pin "1") (pinfunction "1_1") (pintype "passive"))
      (node (ref "C33") (pin "1") (pinfunction "1_1") (pintype "passive"))
      (node (ref "C4") (pin "1") (pinfunction "1_1") (pintype "passive"))
      (node (ref "C5") (pin "2") (pinfunction "2_2") (pintype "passive"))
      (node (ref "C6") (pin "1") (pinfunction "1_1") (pintype "passive"))
      (node (ref "C7") (pin "1") (pinfunction "1_1") (pintype "passive"))
      (node (ref "C8") (pin "1") (pinfunction "1_1") (pintype "passive"))
      (node (ref "C9") (pin "1") (pinfunction "1_1") (pintype "passive"))
      (node (ref "HST_D") (pin "3") (pinfunction "3_3") (pintype "passive"))
      (node (ref "IPX") (pin "1") (pinfunction "1_1") (pintype "passive"))
      (node (ref "IPX") (pin "3") (pinfunction "3_3") (pintype "passive"))
      (node (ref "IPX2") (pin "1") (pinfunction "GND_1") (pintype "passive"))
      (node (ref "IPX2") (pin "3") (pinfunction "GND_3") (pintype "passive"))
      (node (ref "LED1") (pin "K") (pinfunction "K_K") (pintype "passive"))
      (node (ref "LED2") (pin "K") (pinfunction "K_K") (pintype "passive"))
      (node (ref "L_HAN") (pin "1") (pinfunction "1_1") (pintype "passive"))
      (node (ref "L_OFF") (pin "1") (pinfunction "1_1") (pintype "passive"))
      (node (ref "L_ON") (pin "1") (pinfunction "1_1") (pintype "passive"))
      (node (ref "P_6V") (pin "2") (pinfunction "2_2") (pintype "passive"))
      (node (ref "Q1") (pin "2") (pinfunction "E_2") (pintype "passive"))
      (node (ref "Q2") (pin "2") (pinfunction "E_2") (pintype "passive"))
      (node (ref "Q3") (pin "2") (pinfunction "E_2") (pintype "passive"))
      (node (ref "Q4") (pin "2") (pinfunction "E_2") (pintype "passive"))
      (node (ref "Q5") (pin "2") (pinfunction "E_2") (pintype "passive"))
      (node (ref "R19") (pin "1") (pinfunction "1_1") (pintype "passive"))
      (node (ref "R2") (pin "2") (pinfunction "2_2") (pintype "passive"))
      (node (ref "R20") (pin "2") (pinfunction "2_2") (pintype "passive"))
      (node (ref "R22") (pin "1") (pinfunction "1_1") (pintype "passive"))
      (node (ref "R35") (pin "2") (pinfunction "2_2") (pintype "passive"))
      (node (ref "R4") (pin "1") (pinfunction "1_1") (pintype "passive"))
      (node (ref "R5") (pin "1") (pinfunction "1_1") (pintype "passive"))
      (node (ref "RELAY1") (pin "5") (pinfunction "CLO_5") (pintype "passive"))
      (node (ref "RELAY2") (pin "5") (pinfunction "CLO_5") (pintype "passive"))
      (node (ref "RELAY3") (pin "5") (pinfunction "CLO_5") (pintype "passive"))
      (node (ref "SWD") (pin "3") (pinfunction "3_3") (pintype "passive"))
      (node (ref "U2") (pin "1") (pinfunction "GND_1") (pintype "passive"))
      (node (ref "U3") (pin "3") (pinfunction "GND_3") (pintype "passive"))
      (node (ref "U4") (pin "1") (pinfunction "A0_1") (pintype "passive"))
      (node (ref "U4") (pin "2") (pinfunction "A1_2") (pintype "passive"))
      (node (ref "U4") (pin "3") (pinfunction "A2_3") (pintype "passive"))
      (node (ref "U4") (pin "4") (pinfunction "GND_4") (pintype "passive"))
      (node (ref "U4") (pin "7") (pinfunction "WP_7") (pintype "passive"))
      (node (ref "U5") (pin "12") (pinfunction "VSSA_12") (pintype "passive"))
      (node (ref "U5") (pin "18") (pinfunction "VSS_18") (pintype "passive"))
      (node (ref "U5") (pin "31") (pinfunction "VSS_31") (pintype "passive"))
      (node (ref "U5") (pin "47") (pinfunction "VSS_47") (pintype "passive"))
      (node (ref "U5") (pin "63") (pinfunction "VSS_63") (pintype "passive"))
      (node (ref "U6") (pin "10") (pinfunction "GND_10") (pintype "passive"))
      (node (ref "U6") (pin "12") (pinfunction "GND_12") (pintype "passive"))
      (node (ref "U6") (pin "24") (pinfunction "GND_24") (pintype "passive"))
      (node (ref "U7") (pin "1") (pinfunction "AGND_1") (pintype "passive"))
      (node (ref "U7") (pin "31") (pinfunction "SIM_GND_31") (pintype "passive"))
      (node (ref "U7") (pin "35") (pinfunction "GND_35") (pintype "passive"))
      (node (ref "U7") (pin "36") (pinfunction "GND_36") (pintype "passive"))
      (node (ref "U7") (pin "37") (pinfunction "GND_37") (pintype "passive"))
      (node (ref "U7") (pin "38") (pinfunction "GND_38") (pintype "passive"))
      (node (ref "U7") (pin "40") (pinfunction "GND_40") (pintype "passive"))
      (node (ref "U8") (pin "1") (pinfunction "GND_1") (pintype "passive"))
      (node (ref "U9") (pin "2") (pinfunction "A_2") (pintype "passive"))
      (node (ref "UART1") (pin "3") (pinfunction "3_3") (pintype "passive"))
      (node (ref "UART2") (pin "4") (pinfunction "4_4") (pintype "passive"))
      (node (ref "UART4") (pin "3") (pinfunction "3_3") (pintype "passive"))
    )
    (net (code "37") (name "GPS_VCC_EN") (class "Default")
      (node (ref "D2") (pin "1") (pinfunction "A_1") (pintype "passive"))
      (node (ref "R23") (pin "1") (pinfunction "1_1") (pintype "passive"))
      (node (ref "RELAY3") (pin "2") (pinfunction "PUB_2") (pintype "passive"))
      (node (ref "U6") (pin "23") (pinfunction "VCC_23") (pintype "passive"))
    )
    (net (code "38") (name "Net-(D2-K)") (class "Default")
      (node (ref "D2") (pin "2") (pinfunction "K_2") (pintype "passive"))
      (node (ref "R26") (pin "2") (pinfunction "2_2") (pintype "passive"))
    )
    (net (code "39") (name "Net-(D3-A)") (class "Default")
      (node (ref "D1") (pin "2") (pintype "passive"))
      (node (ref "D3") (pin "1") (pinfunction "A_1") (pintype "passive"))
    )
    (net (code "40") (name "Net-(D3-K)") (class "Default")
      (node (ref "C1") (pin "1") (pinfunction "1_1") (pintype "passive"))
      (node (ref "D3") (pin "2") (pinfunction "K_2") (pintype "passive"))
      (node (ref "R1") (pin "2") (pinfunction "2_2") (pintype "passive"))
      (node (ref "U2") (pin "3") (pinfunction "IN_3") (pintype "passive"))
    )
    (net (code "41") (name "Net-(G_L-PadA)") (class "Default")
      (node (ref "G_L") (pin "A") (pinfunction "A_A") (pintype "passive"))
      (node (ref "R23") (pin "2") (pinfunction "2_2") (pintype "passive"))
    )
    (net (code "42") (name "Net-(IPX-Pad2)") (class "Default")
      (node (ref "IPX") (pin "2") (pinfunction "2_2") (pintype "passive"))
      (node (ref "R36") (pin "2") (pinfunction "2_2") (pintype "passive"))
    )
    (net (code "43") (name "Net-(IPX2-DATA)") (class "Default")
      (node (ref "IPX2") (pin "2") (pinfunction "DATA_2") (pintype "passive"))
      (node (ref "U6") (pin "11") (pinfunction "RF_IN_11") (pintype "passive"))
    )
    (net (code "44") (name "Net-(LED1-PadA)") (class "Default")
      (node (ref "LED1") (pin "A") (pinfunction "A_A") (pintype "passive"))
      (node (ref "R33") (pin "1") (pinfunction "1_1") (pintype "passive"))
    )
    (net (code "45") (name "Net-(LED2-PadA)") (class "Default")
      (node (ref "LED2") (pin "A") (pinfunction "A_A") (pintype "passive"))
      (node (ref "R34") (pin "1") (pinfunction "1_1") (pintype "passive"))
    )
    (net (code "46") (name "Net-(Q1-B)") (class "Default")
      (node (ref "Q1") (pin "1") (pinfunction "B_1") (pintype "passive"))
      (node (ref "R9") (pin "2") (pinfunction "2_2") (pintype "passive"))
    )
    (net (code "47") (name "Net-(Q1-C)") (class "Default")
      (node (ref "C7") (pin "2") (pinfunction "2_2") (pintype "passive"))
      (node (ref "Q1") (pin "3") (pinfunction "C_3") (pintype "passive"))
      (node (ref "R8") (pin "1") (pinfunction "1_1") (pintype "passive"))
      (node (ref "RELAY1") (pin "3") (pinfunction "CTRB_3") (pintype "passive"))
    )
    (net (code "48") (name "Net-(Q2-B)") (class "Default")
      (node (ref "Q2") (pin "1") (pinfunction "B_1") (pintype "passive"))
      (node (ref "R11") (pin "2") (pinfunction "2_2") (pintype "passive"))
    )
    (net (code "49") (name "Net-(Q2-C)") (class "Default")
      (node (ref "C9") (pin "2") (pinfunction "2_2") (pintype "passive"))
      (node (ref "Q2") (pin "3") (pinfunction "C_3") (pintype "passive"))
      (node (ref "R10") (pin "1") (pinfunction "1_1") (pintype "passive"))
      (node (ref "RELAY2") (pin "3") (pinfunction "CTRB_3") (pintype "passive"))
    )
    (net (code "50") (name "Net-(Q3-B)") (class "Default")
      (node (ref "Q3") (pin "1") (pinfunction "B_1") (pintype "passive"))
      (node (ref "R13") (pin "2") (pinfunction "2_2") (pintype "passive"))
    )
    (net (code "51") (name "Net-(Q3-C)") (class "Default")
      (node (ref "C11") (pin "2") (pinfunction "2_2") (pintype "passive"))
      (node (ref "Q3") (pin "3") (pinfunction "C_3") (pintype "passive"))
      (node (ref "R_L") (pin "2") (pinfunction "2_2") (pintype "passive"))
    )
    (net (code "52") (name "Net-(Q4-B)") (class "Default")
      (node (ref "Q4") (pin "1") (pinfunction "B_1") (pintype "passive"))
      (node (ref "R15") (pin "2") (pinfunction "2_2") (pintype "passive"))
    )
    (net (code "53") (name "Net-(Q4-C)") (class "Default")
      (node (ref "C13") (pin "2") (pinfunction "2_2") (pintype "passive"))
      (node (ref "Q4") (pin "3") (pinfunction "C_3") (pintype "passive"))
      (node (ref "R_BEL") (pin "2") (pinfunction "2_2") (pintype "passive"))
    )
    (net (code "54") (name "Net-(Q5-B)") (class "Default")
      (node (ref "Q5") (pin "1") (pinfunction "B_1") (pintype "passive"))
      (node (ref "R28") (pin "2") (pinfunction "2_2") (pintype "passive"))
    )
    (net (code "55") (name "Net-(Q5-C)") (class "Default")
      (node (ref "C27") (pin "2") (pinfunction "2_2") (pintype "passive"))
      (node (ref "Q5") (pin "3") (pinfunction "C_3") (pintype "passive"))
      (node (ref "R27") (pin "1") (pinfunction "1_1") (pintype "passive"))
      (node (ref "RELAY3") (pin "3") (pinfunction "CTRB_3") (pintype "passive"))
    )
    (net (code "56") (name "Net-(R12-Pad1)") (class "Default")
      (node (ref "R12") (pin "1") (pinfunction "1_1") (pintype "passive"))
      (node (ref "R_L") (pin "1") (pinfunction "1_1") (pintype "passive"))
    )
    (net (code "57") (name "Net-(R14-Pad1)") (class "Default")
      (node (ref "R14") (pin "1") (pinfunction "1_1") (pintype "passive"))
      (node (ref "R_BEL") (pin "1") (pinfunction "1_1") (pintype "passive"))
    )
    (net (code "58") (name "Net-(U3-ADJ)") (class "Default")
      (node (ref "R3") (pin "1") (pinfunction "1_1") (pintype "passive"))
      (node (ref "R4") (pin "2") (pinfunction "2_2") (pintype "passive"))
      (node (ref "U3") (pin "5") (pinfunction "ADJ_5") (pintype "passive"))
    )
    (net (code "59") (name "Net-(U5-BOOT0)") (class "Default")
      (node (ref "R20") (pin "1") (pinfunction "1_1") (pintype "passive"))
      (node (ref "U5") (pin "60") (pinfunction "BOOT0_60") (pintype "passive"))
    )
    (net (code "60") (name "Net-(U5-PB2{slash}BOOT1)") (class "Default")
      (node (ref "R19") (pin "2") (pinfunction "2_2") (pintype "passive"))
      (node (ref "U5") (pin "28") (pinfunction "PB2/BOOT1_28") (pintype "passive"))
    )
    (net (code "61") (name "Net-(U5-PC14{slash}OSC32)") (class "Default")
      (node (ref "C14") (pin "2") (pinfunction "2_2") (pintype "passive"))
      (node (ref "U5") (pin "3") (pinfunction "PC14/OSC32_3") (pintype "passive"))
      (node (ref "Y1") (pin "2") (pinfunction "OSC2_2") (pintype "passive"))
    )
    (net (code "62") (name "Net-(U5-PC15{slash}OSC32)") (class "Default")
      (node (ref "C15") (pin "2") (pinfunction "2_2") (pintype "passive"))
      (node (ref "U5") (pin "4") (pinfunction "PC15/OSC32_4") (pintype "passive"))
      (node (ref "Y1") (pin "1") (pinfunction "OSC1_1") (pintype "passive"))
    )
    (net (code "63") (name "Net-(U5-PD0{slash}OSCIN)") (class "Default")
      (node (ref "C16") (pin "2") (pinfunction "2_2") (pintype "passive"))
      (node (ref "R17") (pin "2") (pinfunction "2_2") (pintype "passive"))
      (node (ref "U5") (pin "5") (pinfunction "PD0/OSCIN_5") (pintype "passive"))
      (node (ref "Y2") (pin "2") (pinfunction "OSC2_2") (pintype "passive"))
    )
    (net (code "64") (name "Net-(U5-PD1{slash}OSCOUT)") (class "Default")
      (node (ref "C17") (pin "2") (pinfunction "2_2") (pintype "passive"))
      (node (ref "R17") (pin "1") (pinfunction "1_1") (pintype "passive"))
      (node (ref "U5") (pin "6") (pinfunction "PD1/OSCOUT_6") (pintype "passive"))
      (node (ref "Y2") (pin "1") (pinfunction "OSC1_1") (pintype "passive"))
    )
    (net (code "65") (name "Net-(U5-VDDA)") (class "Default")
      (node (ref "C18") (pin "2") (pinfunction "2_2") (pintype "passive"))
      (node (ref "R18") (pin "2") (pinfunction "2_2") (pintype "passive"))
      (node (ref "U5") (pin "13") (pinfunction "VDDA_13") (pintype "passive"))
    )
    (net (code "66") (name "Net-(U6-1PPS)") (class "Default")
      (node (ref "G_L") (pin "K") (pinfunction "K_K") (pintype "passive"))
      (node (ref "U6") (pin "3") (pinfunction "1PPS_3") (pintype "passive"))
    )
    (net (code "67") (name "Net-(U6-RXD)") (class "Default")
      (node (ref "R24") (pin "1") (pintype "passive"))
      (node (ref "U6") (pin "21") (pinfunction "RXD_21") (pintype "passive"))
    )
    (net (code "68") (name "Net-(U6-TXD)") (class "Default")
      (node (ref "R25") (pin "1") (pintype "passive"))
      (node (ref "U6") (pin "20") (pinfunction "TXD_20") (pintype "passive"))
    )
    (net (code "69") (name "Net-(U6-V_BCKP)") (class "Default")
      (node (ref "R26") (pin "1") (pinfunction "1_1") (pintype "passive"))
      (node (ref "U6") (pin "22") (pinfunction "V_BCKP_22") (pintype "passive"))
    )
    (net (code "70") (name "Net-(U7-DTR)") (class "Default")
      (node (ref "R30") (pin "2") (pinfunction "2_2") (pintype "passive"))
      (node (ref "U7") (pin "20") (pinfunction "DTR_20") (pintype "passive"))
    )
    (net (code "71") (name "Net-(U7-NETLIGHT)") (class "Default")
      (node (ref "R34") (pin "2") (pinfunction "2_2") (pintype "passive"))
      (node (ref "U7") (pin "13") (pinfunction "NETLIGHT_13") (pintype "passive"))
    )
    (net (code "72") (name "Net-(U7-PWRKEY)") (class "Default")
      (node (ref "R35") (pin "1") (pinfunction "1_1") (pintype "passive"))
      (node (ref "U7") (pin "10") (pinfunction "PWRKEY_10") (pintype "passive"))
    )
    (net (code "73") (name "Net-(U7-RF_ANT)") (class "Default")
      (node (ref "R36") (pin "1") (pinfunction "1_1") (pintype "passive"))
      (node (ref "U7") (pin "39") (pinfunction "RF_ANT_39") (pintype "passive"))
    )
    (net (code "74") (name "Net-(U7-STSTUS)") (class "Default")
      (node (ref "R33") (pin "2") (pinfunction "2_2") (pintype "passive"))
      (node (ref "U7") (pin "12") (pinfunction "STSTUS_12") (pintype "passive"))
    )
    (net (code "75") (name "Net-(U7-VDD_EXT)") (class "Default")
      (node (ref "R30") (pin "1") (pinfunction "1_1") (pintype "passive"))
      (node (ref "U7") (pin "19") (pinfunction "VDD_EXT_19") (pintype "passive"))
    )
    (net (code "76") (name "VCC") (class "Default")
      (node (ref "C19") (pin "2") (pinfunction "2_2") (pintype "passive"))
      (node (ref "C2") (pin "1") (pinfunction "1_1") (pintype "passive"))
      (node (ref "C20") (pin "2") (pinfunction "2_2") (pintype "passive"))
      (node (ref "C21") (pin "1") (pinfunction "1_1") (pintype "passive"))
      (node (ref "C22") (pin "2") (pinfunction "2_2") (pintype "passive"))
      (node (ref "C23") (pin "2") (pinfunction "2_2") (pintype "passive"))
      (node (ref "C5") (pin "1") (pinfunction "1_1") (pintype "passive"))
      (node (ref "R10") (pin "2") (pinfunction "2_2") (pintype "passive"))
      (node (ref "R12") (pin "2") (pinfunction "2_2") (pintype "passive"))
      (node (ref "R16") (pin "2") (pinfunction "2_2") (pintype "passive"))
      (node (ref "R18") (pin "1") (pinfunction "1_1") (pintype "passive"))
      (node (ref "R21") (pin "2") (pinfunction "2_2") (pintype "passive"))
      (node (ref "R27") (pin "2") (pinfunction "2_2") (pintype "passive"))
      (node (ref "R39") (pin "2") (pinfunction "2_2") (pintype "passive"))
      (node (ref "R40") (pin "2") (pinfunction "2_2") (pintype "passive"))
      (node (ref "R6") (pin "2") (pinfunction "2_2") (pintype "passive"))
      (node (ref "R7") (pin "2") (pinfunction "2_2") (pintype "passive"))
      (node (ref "R8") (pin "2") (pinfunction "2_2") (pintype "passive"))
      (node (ref "RELAY1") (pin "1") (pinfunction "CTRA_1") (pintype "passive"))
      (node (ref "RELAY2") (pin "1") (pinfunction "CTRA_1") (pintype "passive"))
      (node (ref "RELAY3") (pin "1") (pinfunction "CTRA_1") (pintype "passive"))
      (node (ref "RELAY3") (pin "4") (pinfunction "OP_4") (pintype "passive"))
      (node (ref "SWD") (pin "4") (pinfunction "4_4") (pintype "passive"))
      (node (ref "U2") (pin "2") (pinfunction "OUT_2") (pintype "passive"))
      (node (ref "U2") (pin "4") (pinfunction "OUT_4") (pintype "passive"))
      (node (ref "U4") (pin "8") (pinfunction "VCC1_8") (pintype "passive"))
      (node (ref "U5") (pin "1") (pinfunction "VBAT_1") (pintype "passive"))
      (node (ref "U5") (pin "19") (pinfunction "VDD_19") (pintype "passive"))
      (node (ref "U5") (pin "32") (pinfunction "VDD_32") (pintype "passive"))
      (node (ref "U5") (pin "48") (pinfunction "VDD_48") (pintype "passive"))
      (node (ref "U5") (pin "64") (pinfunction "VDD_64") (pintype "passive"))
    )
    (net (code "77") (name "VCC4.0V") (class "Default")
      (node (ref "C24") (pin "1") (pinfunction "1_1") (pintype "passive"))
      (node (ref "C25") (pin "1") (pinfunction "1_1") (pintype "passive"))
      (node (ref "C3") (pin "2") (pinfunction "2_2") (pintype "passive"))
      (node (ref "C4") (pin "2") (pinfunction "2_2") (pintype "passive"))
      (node (ref "R3") (pin "2") (pinfunction "2_2") (pintype "passive"))
      (node (ref "R5") (pin "2") (pinfunction "2_2") (pintype "passive"))
      (node (ref "U3") (pin "4") (pinfunction "OUT_4") (pintype "passive"))
      (node (ref "U7") (pin "33") (pinfunction "VBAT_33") (pintype "passive"))
      (node (ref "U7") (pin "34") (pinfunction "VBAT_34") (pintype "passive"))
      (node (ref "UART2") (pin "1") (pinfunction "1_1") (pintype "passive"))
    )
    (net (code "78") (name "VCC6.0V") (class "Default")
      (node (ref "D1") (pin "1") (pintype "passive"))
      (node (ref "P_6V") (pin "1") (pinfunction "1_1") (pintype "passive"))
      (node (ref "R14") (pin "2") (pinfunction "2_2") (pintype "passive"))
      (node (ref "RELAY1") (pin "4") (pinfunction "OP_4") (pintype "passive"))
      (node (ref "RELAY2") (pin "4") (pinfunction "OP_4") (pintype "passive"))
      (node (ref "U3") (pin "1") (pinfunction "EN_1") (pintype "passive"))
      (node (ref "U3") (pin "2") (pinfunction "IN_2") (pintype "passive"))
    )
    (net (code "79") (name "unconnected-(U5-NRST-Pad7)") (class "Default")
      (node (ref "U5") (pin "7") (pinfunction "NRST_7") (pintype "passive"))
    )
    (net (code "80") (name "unconnected-(U5-PA1{slash}ADC1{slash}TIM2_CH2{slash}TIM5_CH2-Pad15)") (class "Default")
      (node (ref "U5") (pin "15") (pinfunction "PA1/ADC1/TIM2_CH2/TIM5_CH2_15") (pintype "passive"))
    )
    (net (code "81") (name "unconnected-(U5-PA6{slash}SPI1_MISO{slash}ADC6{slash}TIM3_CH1{slash}TIM8_BKIN-Pad22)") (class "Default")
      (node (ref "U5") (pin "22") (pinfunction "PA6/SPI1_MISO/ADC6/TIM3_CH1/TIM8_BKIN_22") (pintype "passive"))
    )
    (net (code "82") (name "unconnected-(U5-PA7{slash}SPI1_MOSI{slash}ADC7{slash}TIM3_CH2{slash}TIM8_CH1N-Pad23)") (class "Default")
      (node (ref "U5") (pin "23") (pinfunction "PA7/SPI1_MOSI/ADC7/TIM3_CH2/TIM8_CH1N_23") (pintype "passive"))
    )
    (net (code "83") (name "unconnected-(U5-PA8{slash}TIM1_CH1{slash}MCO-Pad41)") (class "Default")
      (node (ref "U5") (pin "41") (pinfunction "PA8/TIM1_CH1/MCO_41") (pintype "passive"))
    )
    (net (code "84") (name "unconnected-(U5-PA11{slash}CAN_RX{slash}USBDM{slash}TIM1_CH4-Pad44)") (class "Default")
      (node (ref "U5") (pin "44") (pinfunction "PA11/CAN_RX/USBDM/TIM1_CH4_44") (pintype "passive"))
    )
    (net (code "85") (name "unconnected-(U5-PA12{slash}CAN_TX{slash}USBDP{slash}TIM1_ETR-Pad45)") (class "Default")
      (node (ref "U5") (pin "45") (pinfunction "PA12/CAN_TX/USBDP/TIM1_ETR_45") (pintype "passive"))
    )
    (net (code "86") (name "unconnected-(U5-PA15{slash}JTDI{slash}SPI3_NSS{slash}I2S3_WS-Pad50)") (class "Default")
      (node (ref "U5") (pin "50") (pinfunction "PA15/JTDI/SPI3_NSS/I2S3_WS_50") (pintype "passive"))
    )
    (net (code "87") (name "unconnected-(U5-PB3{slash}JTDO{slash}SPI3_SCK{slash}I2S3_CK-Pad55)") (class "Default")
      (node (ref "U5") (pin "55") (pinfunction "PB3/JTDO/SPI3_SCK/I2S3_CK_55") (pintype "passive"))
    )
    (net (code "88") (name "unconnected-(U5-PB4{slash}JNTRST{slash}SPI3_MISO-Pad56)") (class "Default")
      (node (ref "U5") (pin "56") (pinfunction "PB4/JNTRST/SPI3_MISO_56") (pintype "passive"))
    )
    (net (code "89") (name "unconnected-(U5-PB5{slash}I2C1_SMBA{slash}SPI3_MOSI{slash}I2S3_SD-Pad57)") (class "Default")
      (node (ref "U5") (pin "57") (pinfunction "PB5/I2C1_SMBA/SPI3_MOSI/I2S3_SD_57") (pintype "passive"))
    )
    (net (code "90") (name "unconnected-(U5-PB6{slash}I2C1_SCL{slash}TIM4_CH1-Pad58)") (class "Default")
      (node (ref "U5") (pin "58") (pinfunction "PB6/I2C1_SCL/TIM4_CH1_58") (pintype "passive"))
    )
    (net (code "91") (name "unconnected-(U5-PB7{slash}I2C1_SDA{slash}TIM4_CH2-Pad59)") (class "Default")
      (node (ref "U5") (pin "59") (pinfunction "PB7/I2C1_SDA/TIM4_CH2_59") (pintype "passive"))
    )
    (net (code "92") (name "unconnected-(U5-PB8{slash}TIM4_CH3{slash}SDIO_D4-Pad61)") (class "Default")
      (node (ref "U5") (pin "61") (pinfunction "PB8/TIM4_CH3/SDIO_D4_61") (pintype "passive"))
    )
    (net (code "93") (name "unconnected-(U5-PB9{slash}TIM4_CH4{slash}SDIO_D5-Pad62)") (class "Default")
      (node (ref "U5") (pin "62") (pinfunction "PB9/TIM4_CH4/SDIO_D5_62") (pintype "passive"))
    )
    (net (code "94") (name "unconnected-(U5-PB12{slash}SPI2_NSS{slash}I2S2_WS{slash}I2C2_SMBAI{slash}TIM1_BKIN-Pad33)") (class "Default")
      (node (ref "U5") (pin "33") (pinfunction "PB12/SPI2_NSS/I2S2_WS/I2C2_SMBAI/TIM1_BKIN_33") (pintype "passive"))
    )
    (net (code "95") (name "unconnected-(U5-PB13{slash}SPI2_SCK{slash}I2S2_CK{slash}TIM1_CH1N-Pad34)") (class "Default")
      (node (ref "U5") (pin "34") (pinfunction "PB13/SPI2_SCK/I2S2_CK/TIM1_CH1N_34") (pintype "passive"))
    )
    (net (code "96") (name "unconnected-(U5-PB14{slash}SPI2_MISO{slash}TIM1_CH2N-Pad35)") (class "Default")
      (node (ref "U5") (pin "35") (pinfunction "PB14/SPI2_MISO/TIM1_CH2N_35") (pintype "passive"))
    )
    (net (code "97") (name "unconnected-(U5-PB15{slash}SPI2_MOSI{slash}I2S2_SD{slash}TIM1_CH3N-Pad36)") (class "Default")
      (node (ref "U5") (pin "36") (pinfunction "PB15/SPI2_MOSI/I2S2_SD/TIM1_CH3N_36") (pintype "passive"))
    )
    (net (code "98") (name "unconnected-(U5-PC7{slash}I2S3_MCK{slash}TIM8_CH2{slash}SDIO_D7-Pad38)") (class "Default")
      (node (ref "U5") (pin "38") (pinfunction "PC7/I2S3_MCK/TIM8_CH2/SDIO_D7_38") (pintype "passive"))
    )
    (net (code "99") (name "unconnected-(U5-PC8{slash}TIM8_CH3{slash}SDIO_D0-Pad39)") (class "Default")
      (node (ref "U5") (pin "39") (pinfunction "PC8/TIM8_CH3/SDIO_D0_39") (pintype "passive"))
    )
    (net (code "100") (name "unconnected-(U5-PC9{slash}TIM8_CH4{slash}SDIO_D1-Pad40)") (class "Default")
      (node (ref "U5") (pin "40") (pinfunction "PC9/TIM8_CH4/SDIO_D1_40") (pintype "passive"))
    )
    (net (code "101") (name "unconnected-(U5-PC13{slash}ANT1-Pad2)") (class "Default")
      (node (ref "U5") (pin "2") (pinfunction "PC13/ANT1_2") (pintype "passive"))
    )
    (net (code "102") (name "unconnected-(U6-GND-Pad13)") (class "Default")
      (node (ref "U6") (pin "13") (pinfunction "GND_13") (pintype "passive"))
    )
    (net (code "103") (name "unconnected-(U6-NC-Pad1)") (class "Default")
      (node (ref "U6") (pin "1") (pinfunction "NC_1") (pintype "passive"))
    )
    (net (code "104") (name "unconnected-(U6-NC-Pad2)") (class "Default")
      (node (ref "U6") (pin "2") (pinfunction "NC_2") (pintype "passive"))
    )
    (net (code "105") (name "unconnected-(U6-NC-Pad4)") (class "Default")
      (node (ref "U6") (pin "4") (pinfunction "NC_4") (pintype "passive"))
    )
    (net (code "106") (name "unconnected-(U6-NC-Pad5)") (class "Default")
      (node (ref "U6") (pin "5") (pinfunction "NC_5") (pintype "passive"))
    )
    (net (code "107") (name "unconnected-(U6-NC-Pad6)") (class "Default")
      (node (ref "U6") (pin "6") (pinfunction "NC_6") (pintype "passive"))
    )
    (net (code "108") (name "unconnected-(U6-NC-Pad7)") (class "Default")
      (node (ref "U6") (pin "7") (pinfunction "NC_7") (pintype "passive"))
    )
    (net (code "109") (name "unconnected-(U6-NC-Pad9)") (class "Default")
      (node (ref "U6") (pin "9") (pinfunction "NC_9") (pintype "passive"))
    )
    (net (code "110") (name "unconnected-(U6-NC-Pad14)") (class "Default")
      (node (ref "U6") (pin "14") (pinfunction "NC_14") (pintype "passive"))
    )
    (net (code "111") (name "unconnected-(U6-NC-Pad15)") (class "Default")
      (node (ref "U6") (pin "15") (pinfunction "NC_15") (pintype "passive"))
    )
    (net (code "112") (name "unconnected-(U6-NC-Pad16)") (class "Default")
      (node (ref "U6") (pin "16") (pinfunction "NC_16") (pintype "passive"))
    )
    (net (code "113") (name "unconnected-(U6-NC-Pad17)") (class "Default")
      (node (ref "U6") (pin "17") (pinfunction "NC_17") (pintype "passive"))
    )
    (net (code "114") (name "unconnected-(U6-RSTN-Pad8)") (class "Default")
      (node (ref "U6") (pin "8") (pinfunction "RSTN_8") (pintype "passive"))
    )
    (net (code "115") (name "unconnected-(U6-SCL{slash}NC-Pad19)") (class "Default")
      (node (ref "U6") (pin "19") (pinfunction "SCL/NC_19") (pintype "passive"))
    )
    (net (code "116") (name "unconnected-(U6-SDA{slash}NC-Pad18)") (class "Default")
      (node (ref "U6") (pin "18") (pinfunction "SDA/NC_18") (pintype "passive"))
    )
    (net (code "117") (name "unconnected-(U7-ADC-Pad16)") (class "Default")
      (node (ref "U7") (pin "16") (pinfunction "ADC_16") (pintype "passive"))
    )
    (net (code "118") (name "unconnected-(U7-CTS-Pad23)") (class "Default")
      (node (ref "U7") (pin "23") (pinfunction "CTS_23") (pintype "passive"))
    )
    (net (code "119") (name "unconnected-(U7-DCD-Pad25)") (class "Default")
      (node (ref "U7") (pin "25") (pinfunction "DCD_25") (pintype "passive"))
    )
    (net (code "120") (name "unconnected-(U7-GPIO-Pad17)") (class "Default")
      (node (ref "U7") (pin "17") (pinfunction "GPIO_17") (pintype "passive"))
    )
    (net (code "121") (name "unconnected-(U7-GPIO-Pad18)") (class "Default")
      (node (ref "U7") (pin "18") (pinfunction "GPIO_18") (pintype "passive"))
    )
    (net (code "122") (name "unconnected-(U7-LOUDSPKN-Pad8)") (class "Default")
      (node (ref "U7") (pin "8") (pinfunction "LOUDSPKN_8") (pintype "passive"))
    )
    (net (code "123") (name "unconnected-(U7-LOUDSPKP-Pad9)") (class "Default")
      (node (ref "U7") (pin "9") (pinfunction "LOUDSPKP_9") (pintype "passive"))
    )
    (net (code "124") (name "unconnected-(U7-MIC1N-Pad5)") (class "Default")
      (node (ref "U7") (pin "5") (pinfunction "MIC1N_5") (pintype "passive"))
    )
    (net (code "125") (name "unconnected-(U7-MIC1P-Pad4)") (class "Default")
      (node (ref "U7") (pin "4") (pinfunction "MIC1P_4") (pintype "passive"))
    )
    (net (code "126") (name "unconnected-(U7-MIC2N-Pad3)") (class "Default")
      (node (ref "U7") (pin "3") (pinfunction "MIC2N_3") (pintype "passive"))
    )
    (net (code "127") (name "unconnected-(U7-MIC2P-Pad2)") (class "Default")
      (node (ref "U7") (pin "2") (pinfunction "MIC2P_2") (pintype "passive"))
    )
    (net (code "128") (name "unconnected-(U7-RESET-Pad11)") (class "Default")
      (node (ref "U7") (pin "11") (pinfunction "RESET_11") (pintype "passive"))
    )
    (net (code "129") (name "unconnected-(U7-RI-Pad26)") (class "Default")
      (node (ref "U7") (pin "26") (pinfunction "RI_26") (pintype "passive"))
    )
    (net (code "130") (name "unconnected-(U7-RTS-Pad24)") (class "Default")
      (node (ref "U7") (pin "24") (pinfunction "RTS_24") (pintype "passive"))
    )
    (net (code "131") (name "unconnected-(U7-SPK1N-Pad6)") (class "Default")
      (node (ref "U7") (pin "6") (pinfunction "SPK1N_6") (pintype "passive"))
    )
    (net (code "132") (name "unconnected-(U7-SPK1P-Pad7)") (class "Default")
      (node (ref "U7") (pin "7") (pinfunction "SPK1P_7") (pintype "passive"))
    )
    (net (code "133") (name "unconnected-(U7-VRTC-Pad32)") (class "Default")
      (node (ref "U7") (pin "32") (pinfunction "VRTC_32") (pintype "passive"))
    )
    (net (code "134") (name "unconnected-(U8-VPP-Pad3)") (class "Default")
      (node (ref "U8") (pin "3") (pinfunction "VPP_3") (pintype "passive"))
    )
    (net (code "135") (name "unconnected-(U9-K2-Pad3)") (class "Default")
      (node (ref "U9") (pin "3") (pinfunction "K2_3") (pintype "passive"))
    )
  )
)
